# TMC5130_3D_Printer_BOARD_V_2.net
KiCad netlist of a schematic drawn in EAGLE
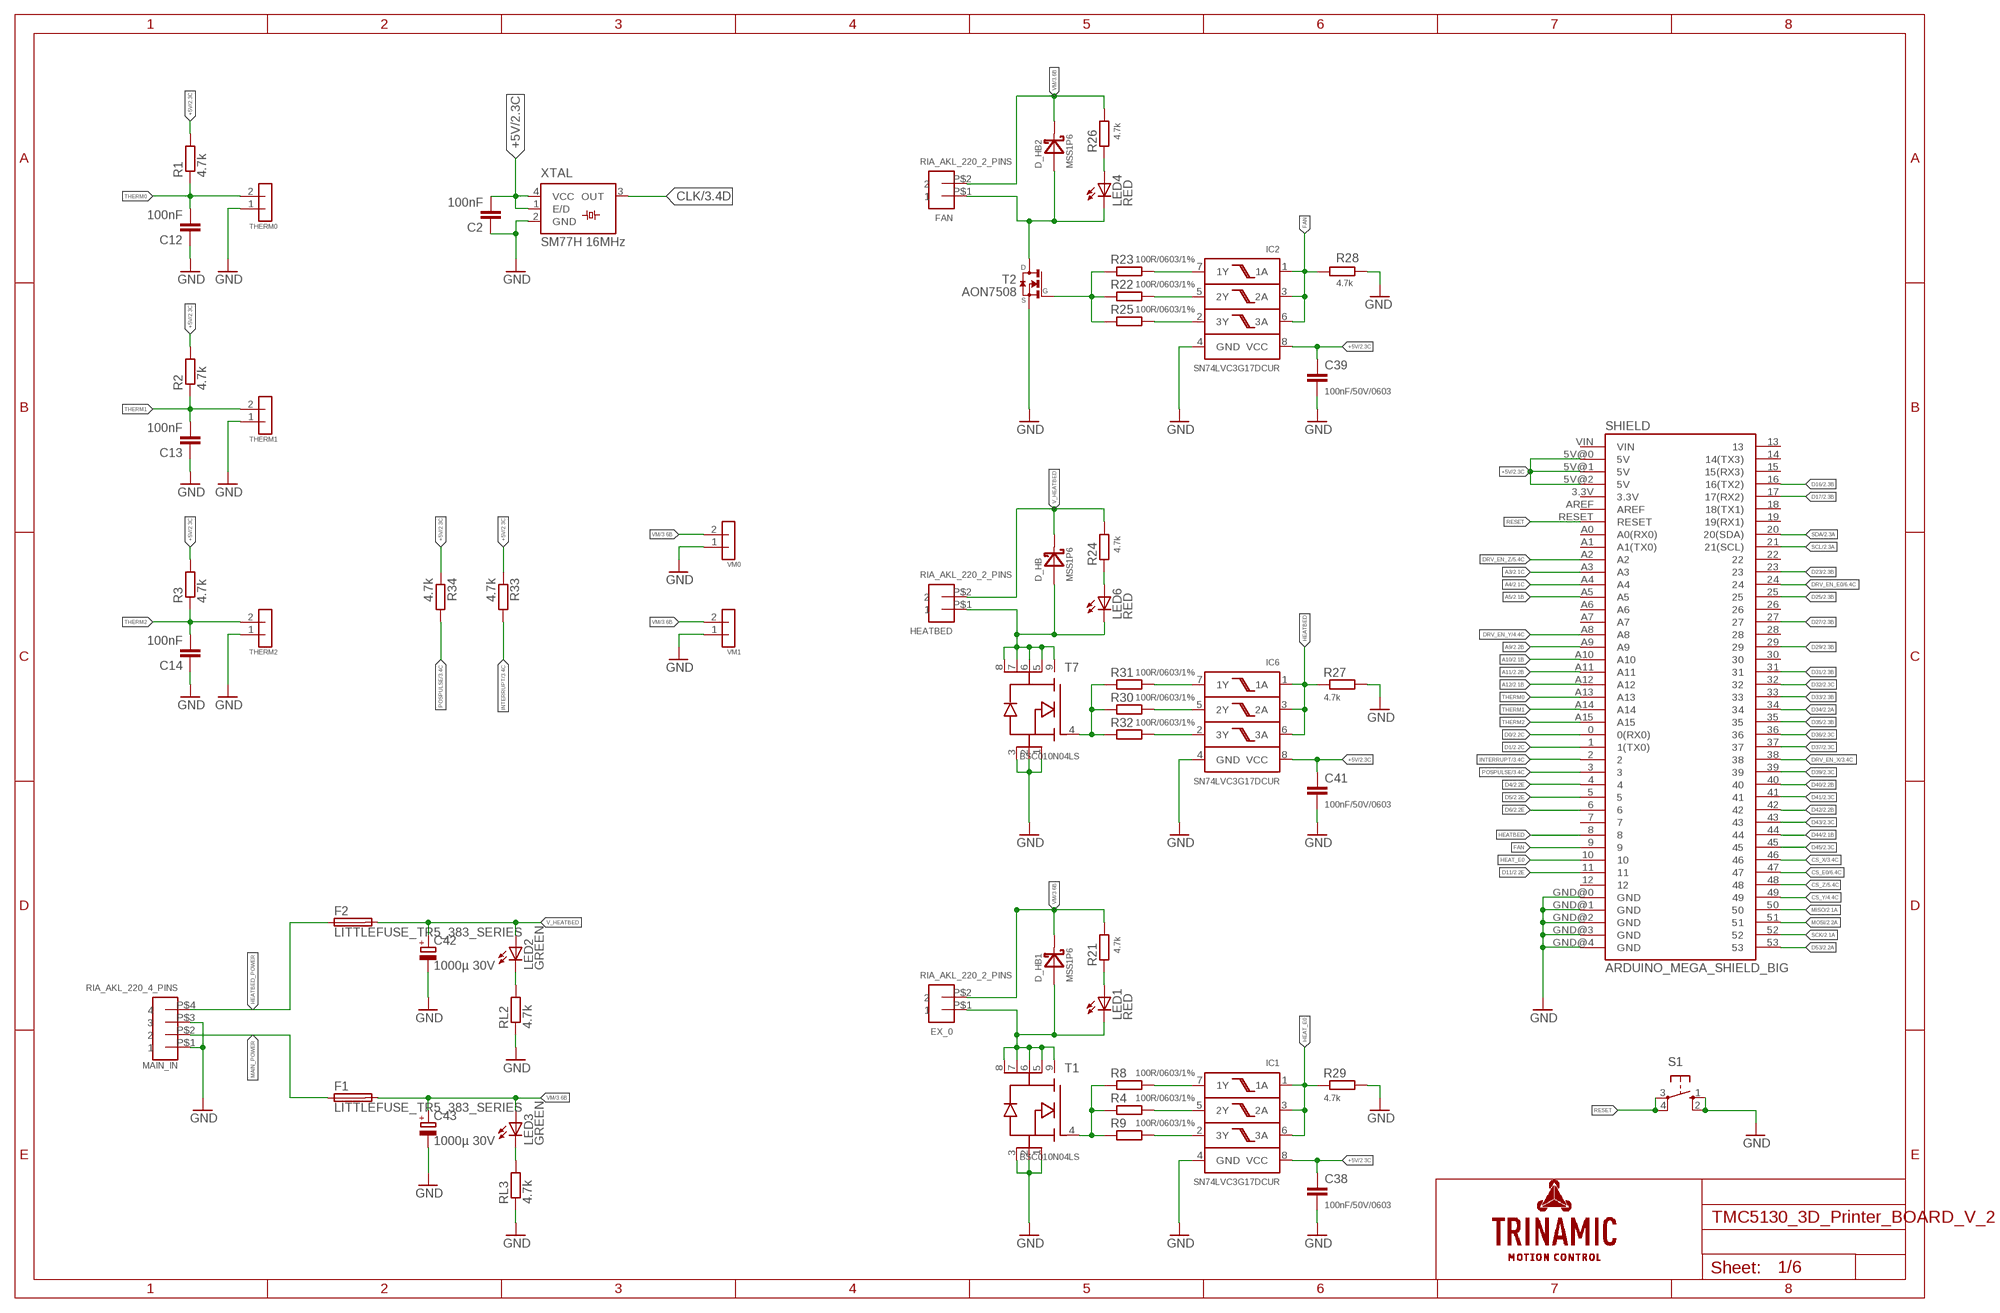
[diagram p0: schematic, sheet 1]
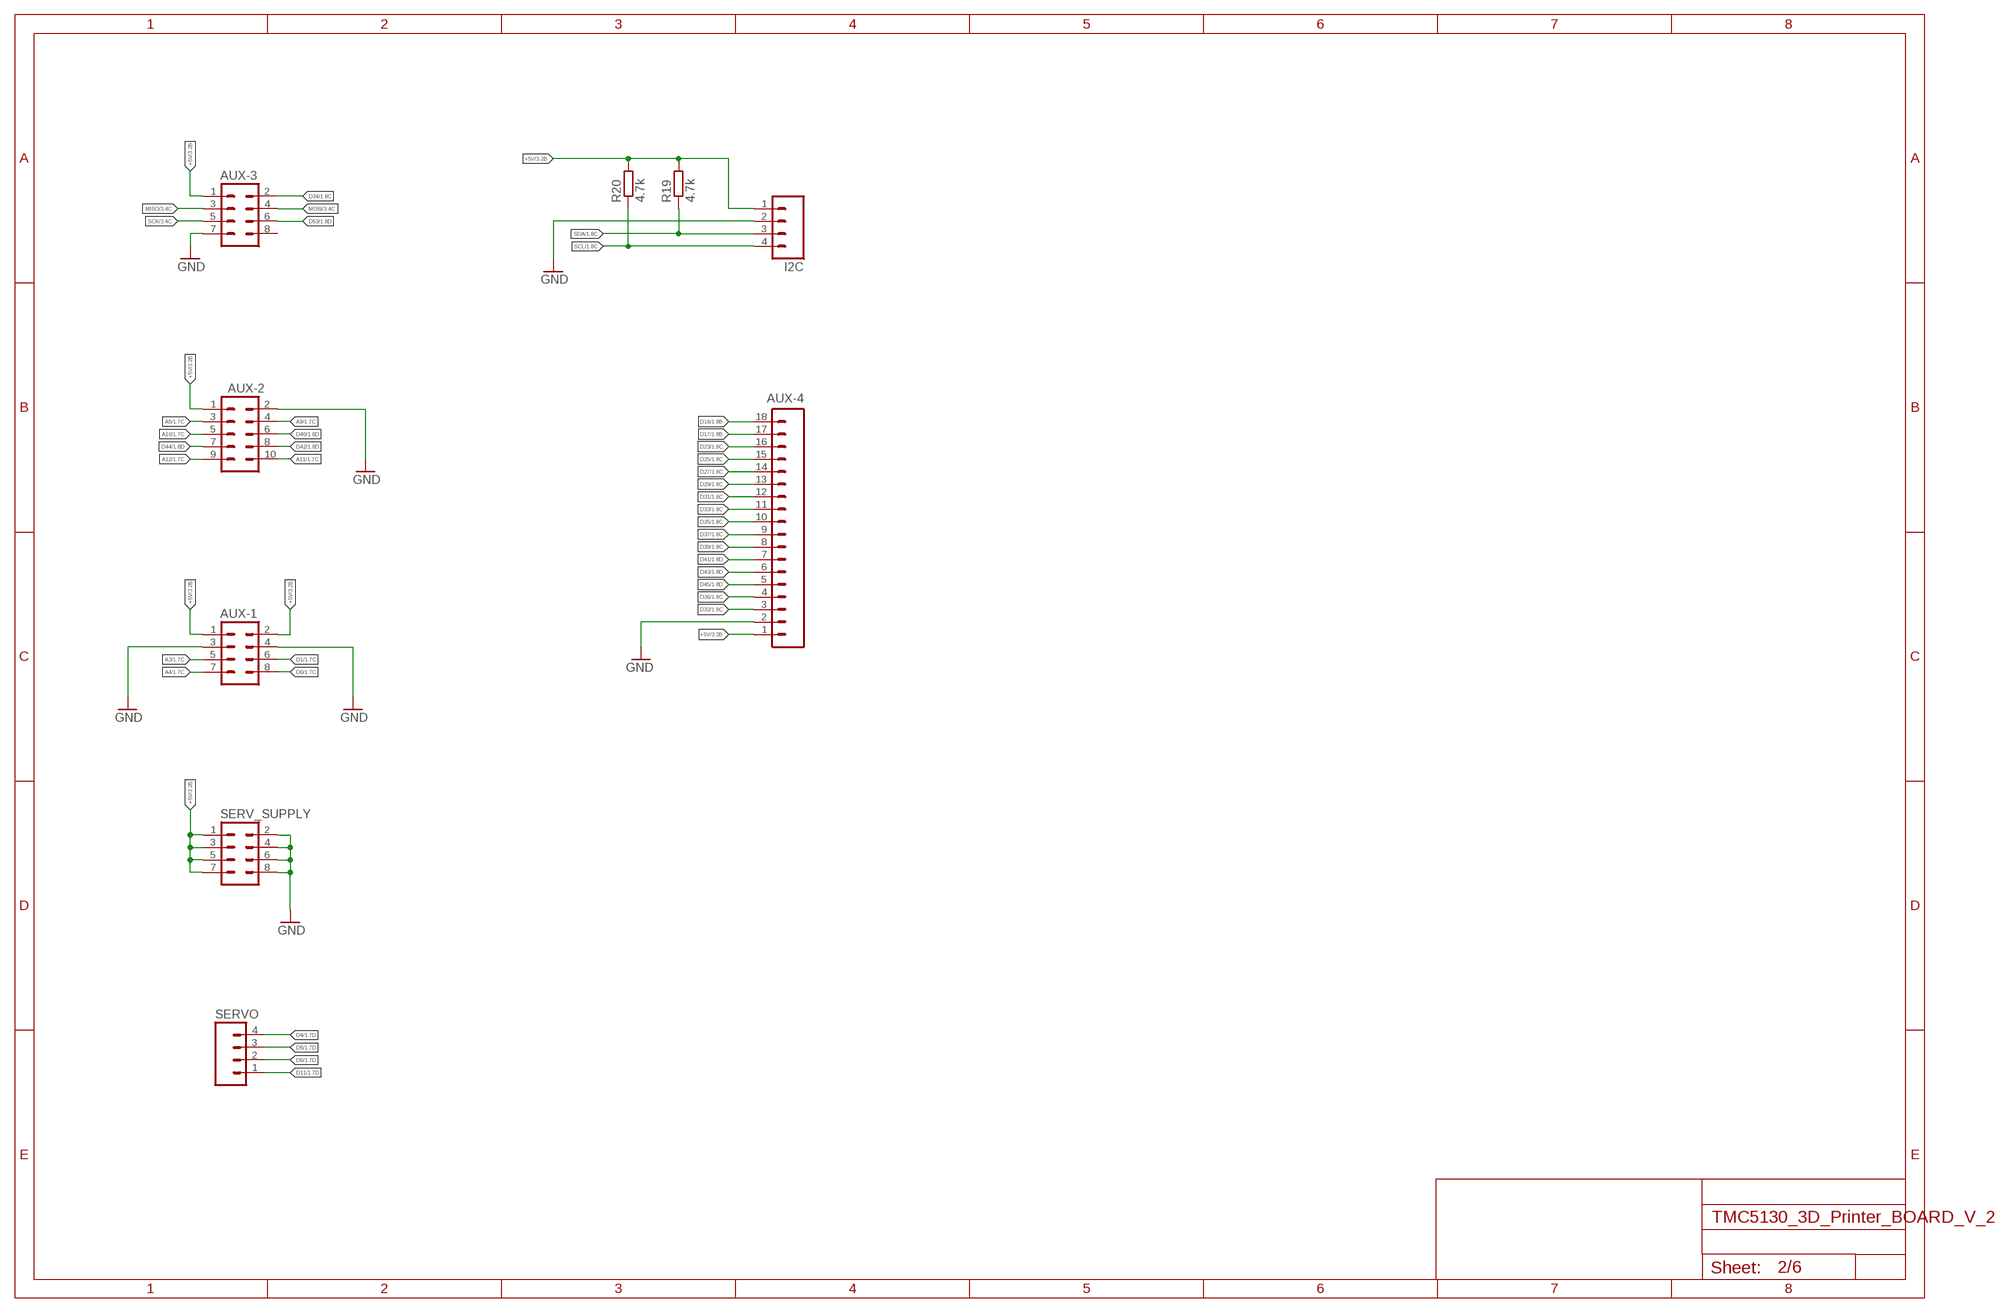
[diagram p1: schematic, sheet 2]
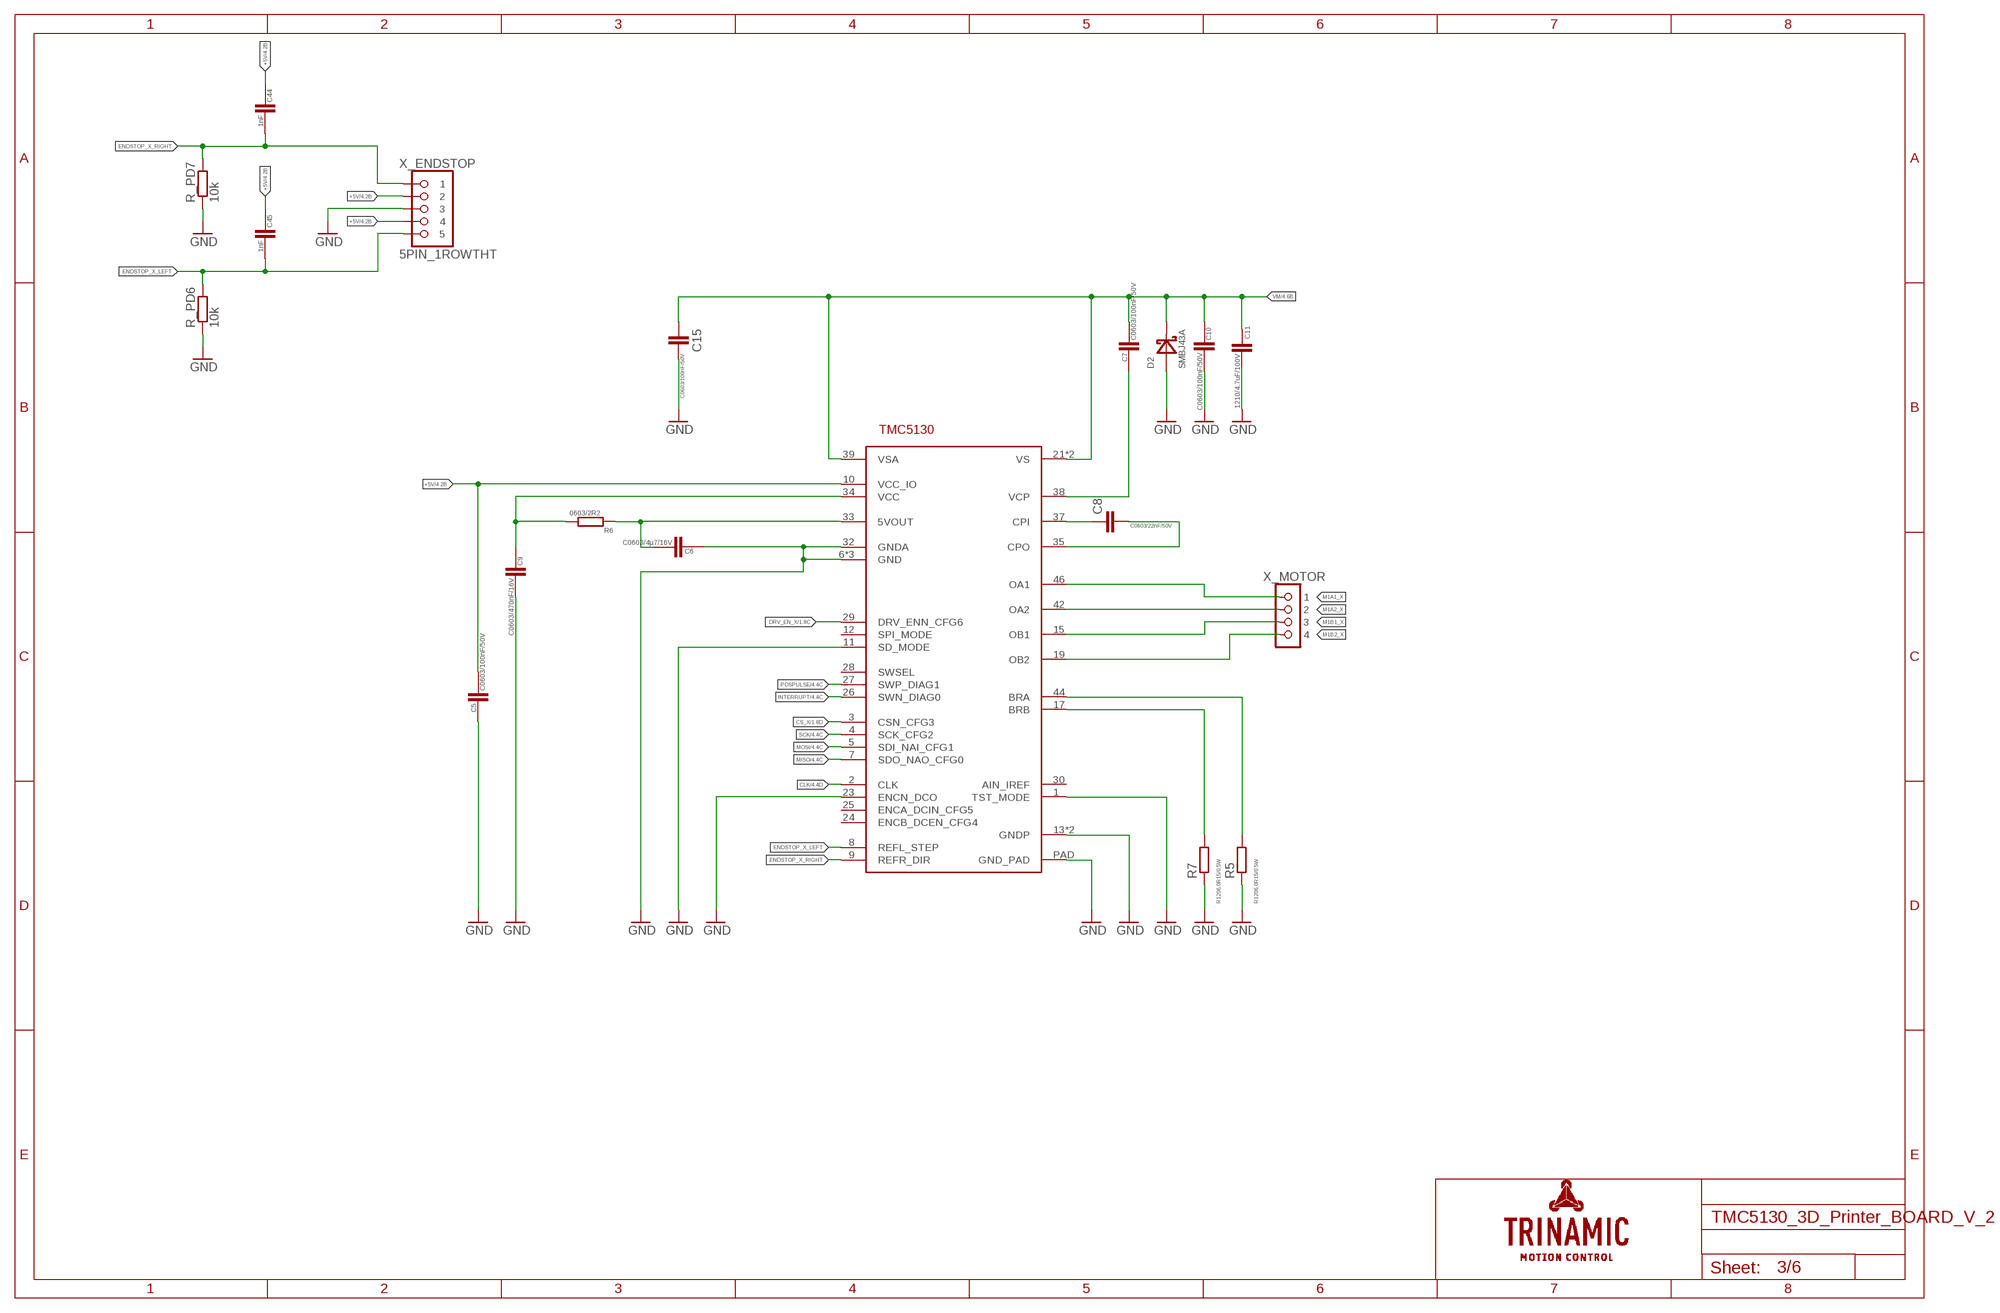
[diagram p2: schematic, sheet 3]
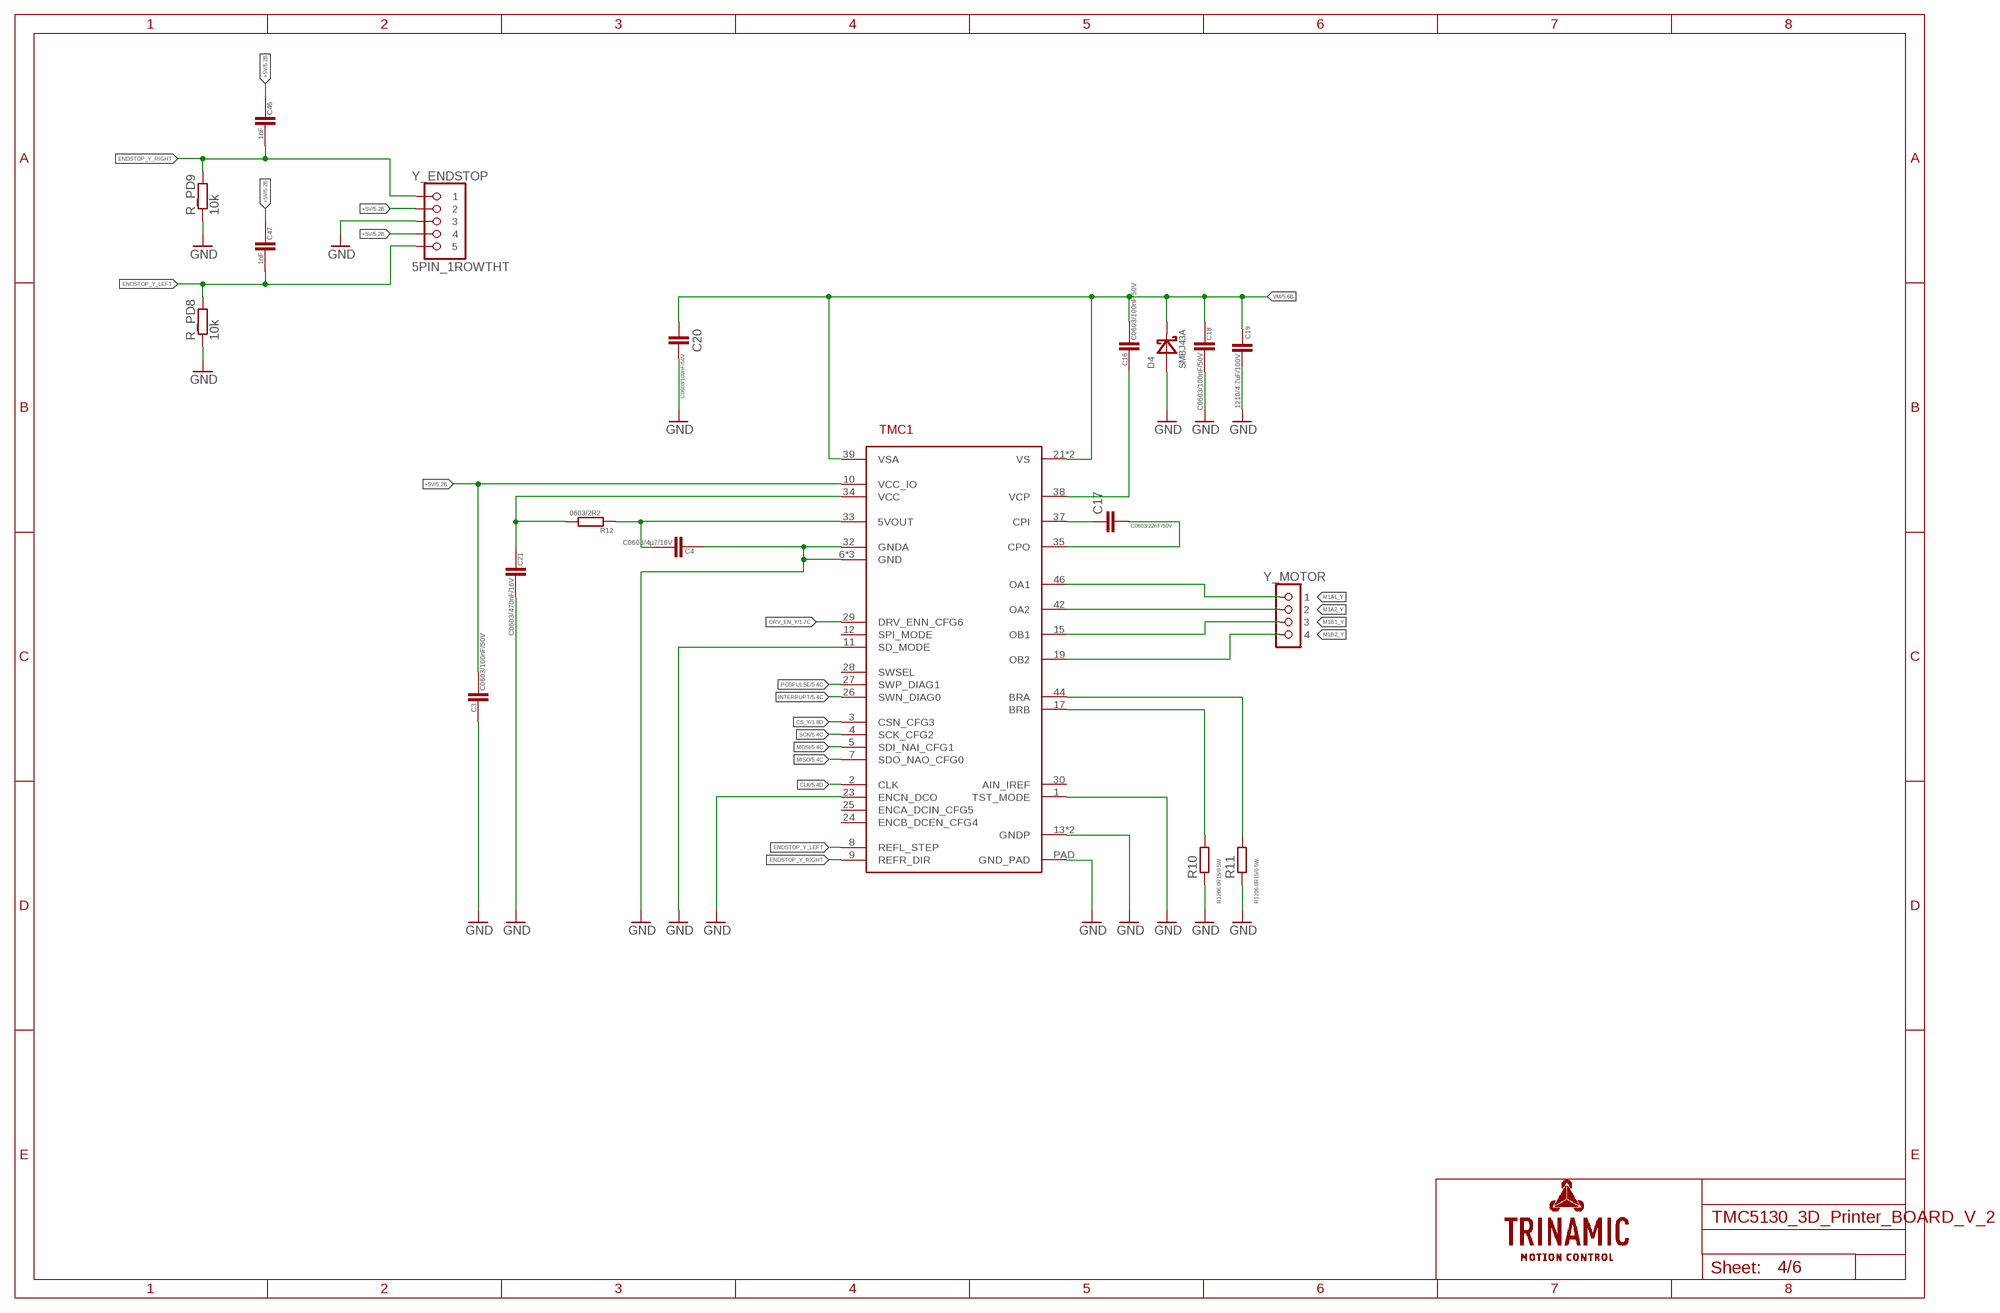
[diagram p3: schematic, sheet 4]
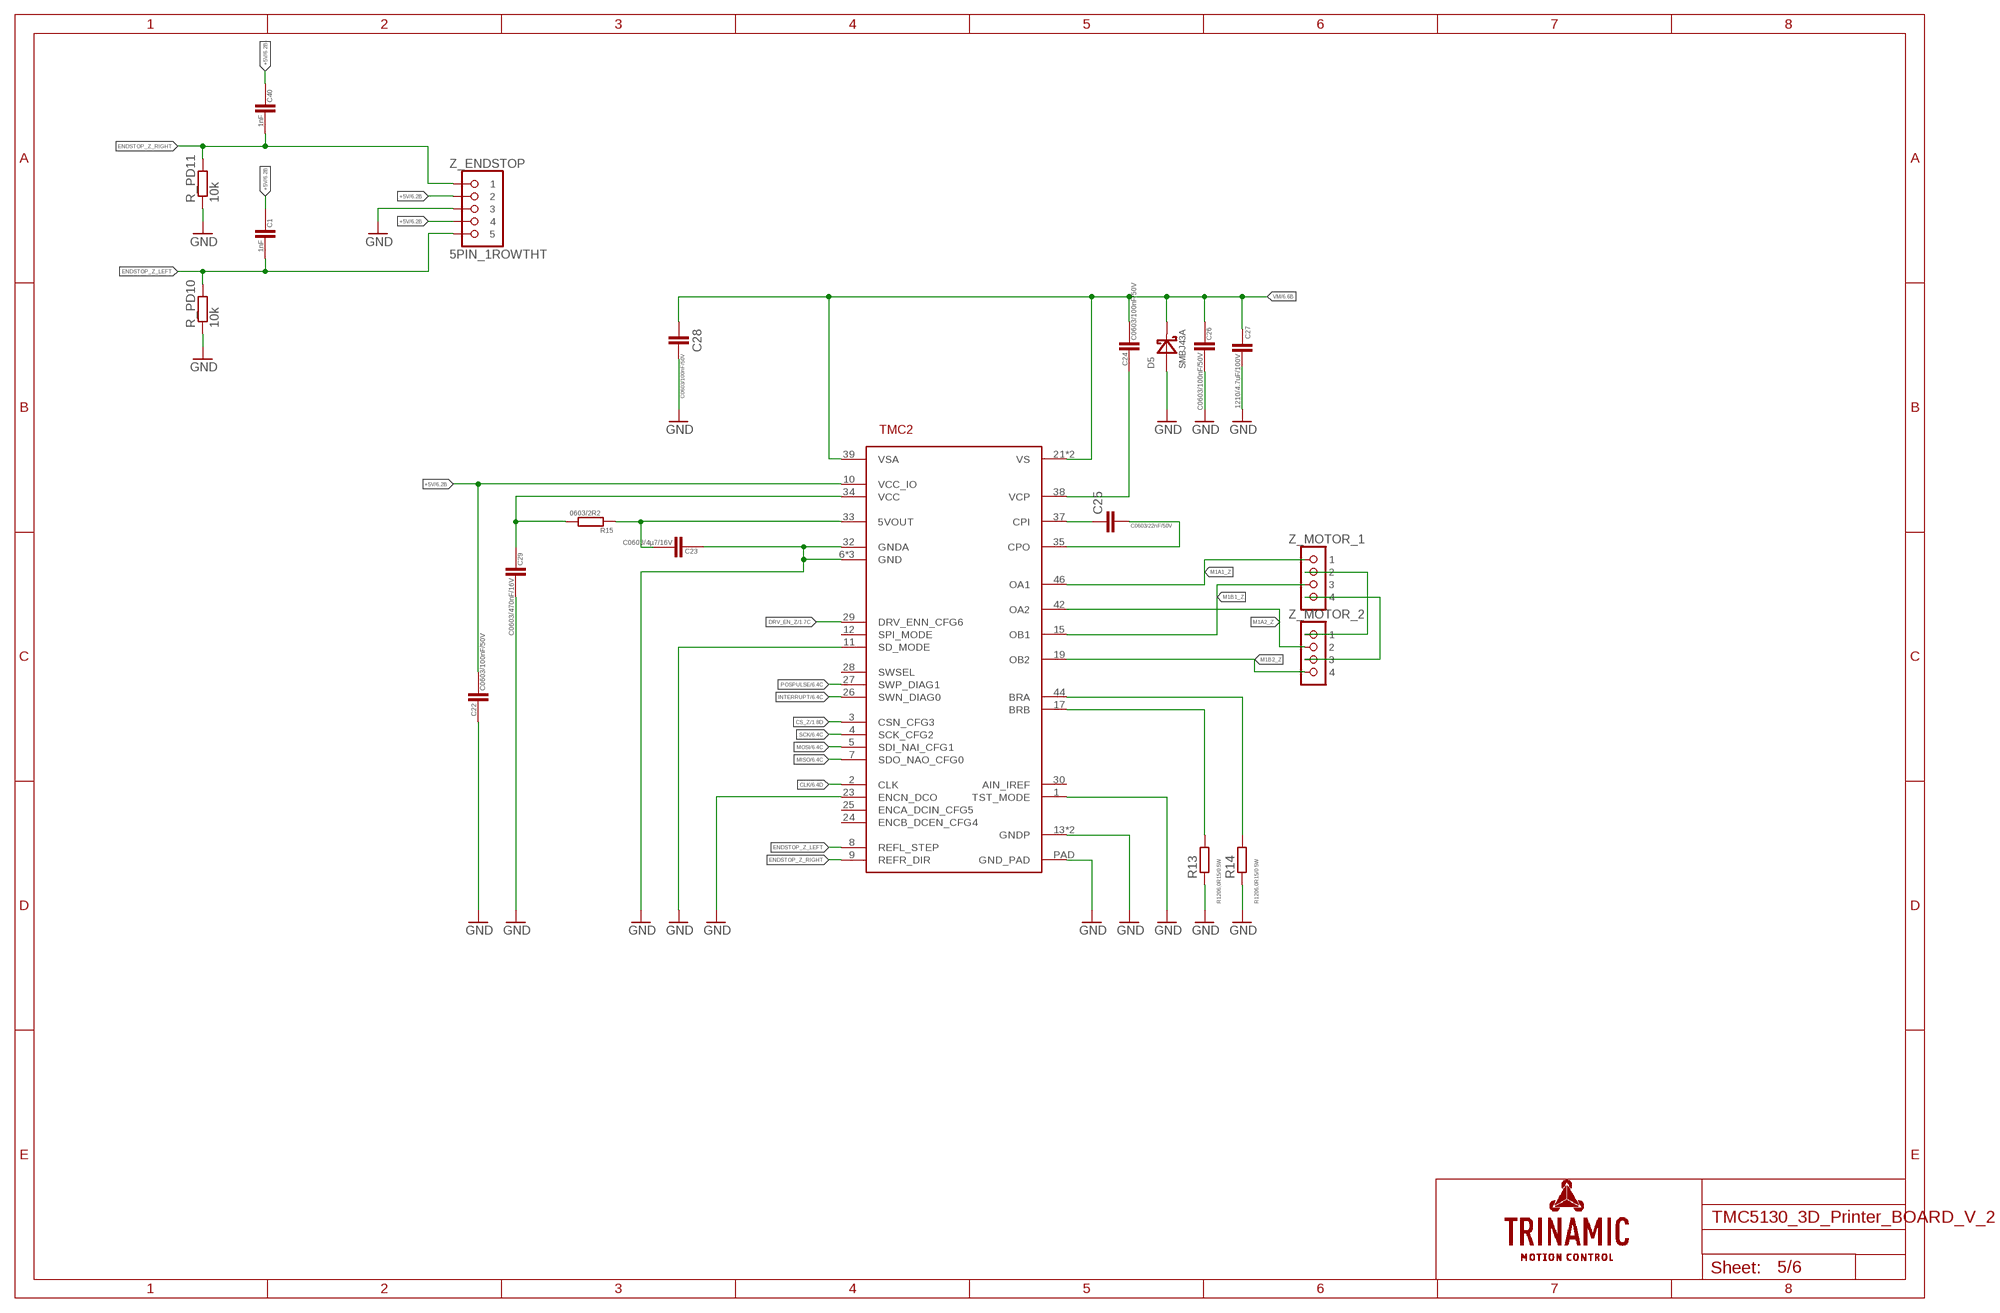
[diagram p4: schematic, sheet 5]
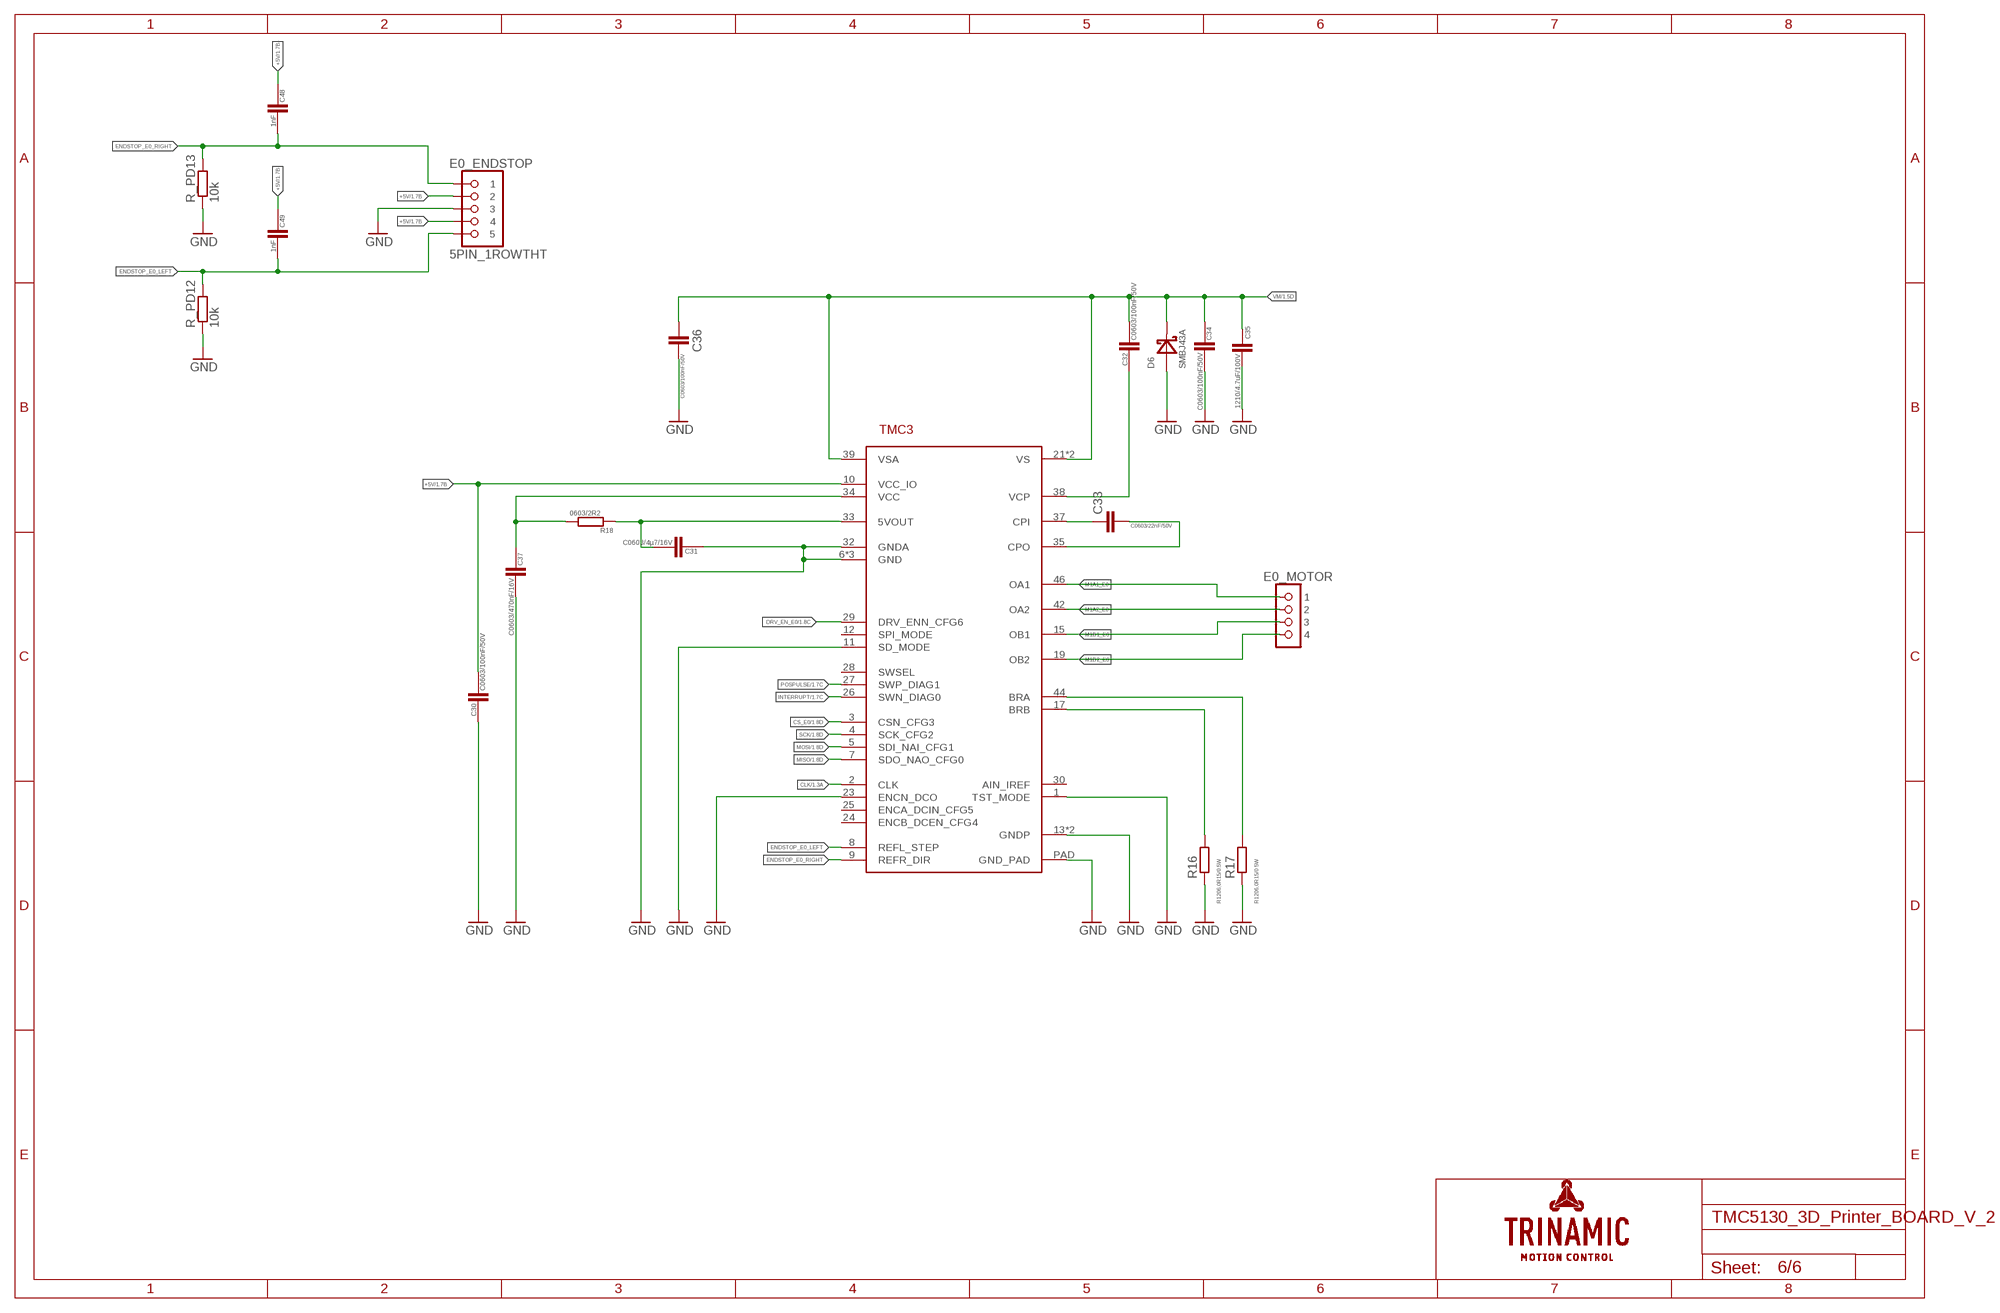
[diagram p5: schematic, sheet 6]

(export (version "E")
  (design (tool "Eeschema 10.0.6"))
  (components
    (comp (ref "C2")
      (value "100nF")
      (footprint "eagle-import:C0603")
      (libsource (lib "eagle-import") (part "C-EUC0603"))
    )
    (comp (ref "C12")
      (value "100nF")
      (footprint "eagle-import:C0603")
      (libsource (lib "eagle-import") (part "C-EUC0603"))
    )
    (comp (ref "C13")
      (value "100nF")
      (footprint "eagle-import:C0603")
      (libsource (lib "eagle-import") (part "C-EUC0603"))
    )
    (comp (ref "C14")
      (value "100nF")
      (footprint "eagle-import:C0603")
      (libsource (lib "eagle-import") (part "C-EUC0603"))
    )
    (comp (ref "C38")
      (value "100nF/50V/0603")
      (footprint "eagle-import:C0603")
      (libsource (lib "eagle-import") (part "C-EUC0603"))
    )
    (comp (ref "C39")
      (value "100nF/50V/0603")
      (footprint "eagle-import:C0603")
      (libsource (lib "eagle-import") (part "C-EUC0603"))
    )
    (comp (ref "C41")
      (value "100nF/50V/0603")
      (footprint "eagle-import:C0603")
      (libsource (lib "eagle-import") (part "C-EUC0603"))
    )
    (comp (ref "C42")
      (value "1000µ 30V")
      (footprint "eagle-import:E5-10,5")
      (libsource (lib "eagle-import") (part "CPOL-EUE5-10.5"))
    )
    (comp (ref "C43")
      (value "1000µ 30V")
      (footprint "eagle-import:E5-10,5")
      (libsource (lib "eagle-import") (part "CPOL-EUE5-10.5"))
    )
    (comp (ref "D_HB")
      (value "MSS1P6")
      (footprint "eagle-import:MICRO_SMP")
      (libsource (lib "eagle-import") (part "MSS1P6"))
    )
    (comp (ref "D_HB1")
      (value "MSS1P6")
      (footprint "eagle-import:MICRO_SMP")
      (libsource (lib "eagle-import") (part "MSS1P6"))
    )
    (comp (ref "D_HB2")
      (value "MSS1P6")
      (footprint "eagle-import:MICRO_SMP")
      (libsource (lib "eagle-import") (part "MSS1P6"))
    )
    (comp (ref "EX_0")
      (value "RIA_AKL_220_2_PINS")
      (footprint "eagle-import:RIA_AKL_220_2_PINS")
      (libsource (lib "eagle-import") (part "RIA_AKL_220_2_PINS"))
    )
    (comp (ref "F1")
      (value "LITTLEFUSE_TR5_383_SERIES")
      (footprint "eagle-import:LITTLEFUSE_TR5_383_SERIES")
      (libsource (lib "eagle-import") (part "LITTLEFUSE_TR5_383_SERIES"))
    )
    (comp (ref "F2")
      (value "LITTLEFUSE_TR5_383_SERIES")
      (footprint "eagle-import:LITTLEFUSE_TR5_383_SERIES")
      (libsource (lib "eagle-import") (part "LITTLEFUSE_TR5_383_SERIES"))
    )
    (comp (ref "FAN")
      (value "RIA_AKL_220_2_PINS")
      (footprint "eagle-import:RIA_AKL_220_2_PINS")
      (libsource (lib "eagle-import") (part "RIA_AKL_220_2_PINS"))
    )
    (comp (ref "HEATBED")
      (value "RIA_AKL_220_2_PINS")
      (footprint "eagle-import:RIA_AKL_220_2_PINS")
      (libsource (lib "eagle-import") (part "RIA_AKL_220_2_PINS"))
    )
    (comp (ref "IC1")
      (value "SN74LVC3G17DCUR")
      (footprint "eagle-import:US8_DCU")
      (libsource (lib "eagle-import") (part "SN74LVC3G17DCUR"))
    )
    (comp (ref "IC2")
      (value "SN74LVC3G17DCUR")
      (footprint "eagle-import:US8_DCU")
      (libsource (lib "eagle-import") (part "SN74LVC3G17DCUR"))
    )
    (comp (ref "IC6")
      (value "SN74LVC3G17DCUR")
      (footprint "eagle-import:US8_DCU")
      (libsource (lib "eagle-import") (part "SN74LVC3G17DCUR"))
    )
    (comp (ref "LED1")
      (value "RED")
      (footprint "eagle-import:CHIPLED_0603")
      (libsource (lib "eagle-import") (part "LEDCHIPLED_0603"))
    )
    (comp (ref "LED2")
      (value "GREEN")
      (footprint "eagle-import:CHIPLED_0603")
      (libsource (lib "eagle-import") (part "LEDCHIPLED_0603"))
    )
    (comp (ref "LED3")
      (value "GREEN")
      (footprint "eagle-import:CHIPLED_0603")
      (libsource (lib "eagle-import") (part "LEDCHIPLED_0603"))
    )
    (comp (ref "LED4")
      (value "RED")
      (footprint "eagle-import:CHIPLED_0603")
      (libsource (lib "eagle-import") (part "LEDCHIPLED_0603"))
    )
    (comp (ref "LED6")
      (value "RED")
      (footprint "eagle-import:CHIPLED_0603")
      (libsource (lib "eagle-import") (part "LEDCHIPLED_0603"))
    )
    (comp (ref "MAIN_IN")
      (value "RIA_AKL_220_4_PINS")
      (footprint "eagle-import:RIA_AKL_220_4_PINS")
      (libsource (lib "eagle-import") (part "RIA_AKL_220_4_PINS"))
    )
    (comp (ref "R1")
      (value "4.7k")
      (footprint "eagle-import:R0603")
      (libsource (lib "eagle-import") (part "R-EU_R0603"))
    )
    (comp (ref "R2")
      (value "4.7k")
      (footprint "eagle-import:R0603")
      (libsource (lib "eagle-import") (part "R-EU_R0603"))
    )
    (comp (ref "R3")
      (value "4.7k")
      (footprint "eagle-import:R0603")
      (libsource (lib "eagle-import") (part "R-EU_R0603"))
    )
    (comp (ref "R4")
      (value "100R/0603/1%")
      (footprint "eagle-import:R0603")
      (libsource (lib "eagle-import") (part "R-EU_R0603"))
    )
    (comp (ref "R8")
      (value "100R/0603/1%")
      (footprint "eagle-import:R0603")
      (libsource (lib "eagle-import") (part "R-EU_R0603"))
    )
    (comp (ref "R9")
      (value "100R/0603/1%")
      (footprint "eagle-import:R0603")
      (libsource (lib "eagle-import") (part "R-EU_R0603"))
    )
    (comp (ref "R21")
      (value "4.7k")
      (footprint "eagle-import:R0603")
      (libsource (lib "eagle-import") (part "R-EU_R0603"))
    )
    (comp (ref "R22")
      (value "100R/0603/1%")
      (footprint "eagle-import:R0603")
      (libsource (lib "eagle-import") (part "R-EU_R0603"))
    )
    (comp (ref "R23")
      (value "100R/0603/1%")
      (footprint "eagle-import:R0603")
      (libsource (lib "eagle-import") (part "R-EU_R0603"))
    )
    (comp (ref "R24")
      (value "4.7k")
      (footprint "eagle-import:R0603")
      (libsource (lib "eagle-import") (part "R-EU_R0603"))
    )
    (comp (ref "R25")
      (value "100R/0603/1%")
      (footprint "eagle-import:R0603")
      (libsource (lib "eagle-import") (part "R-EU_R0603"))
    )
    (comp (ref "R26")
      (value "4.7k")
      (footprint "eagle-import:R0603")
      (libsource (lib "eagle-import") (part "R-EU_R0603"))
    )
    (comp (ref "R27")
      (value "4.7k")
      (footprint "eagle-import:R0603")
      (libsource (lib "eagle-import") (part "R-EU_R0603"))
    )
    (comp (ref "R28")
      (value "4.7k")
      (footprint "eagle-import:R0603")
      (libsource (lib "eagle-import") (part "R-EU_R0603"))
    )
    (comp (ref "R29")
      (value "4.7k")
      (footprint "eagle-import:R0603")
      (libsource (lib "eagle-import") (part "R-EU_R0603"))
    )
    (comp (ref "R30")
      (value "100R/0603/1%")
      (footprint "eagle-import:R0603")
      (libsource (lib "eagle-import") (part "R-EU_R0603"))
    )
    (comp (ref "R31")
      (value "100R/0603/1%")
      (footprint "eagle-import:R0603")
      (libsource (lib "eagle-import") (part "R-EU_R0603"))
    )
    (comp (ref "R32")
      (value "100R/0603/1%")
      (footprint "eagle-import:R0603")
      (libsource (lib "eagle-import") (part "R-EU_R0603"))
    )
    (comp (ref "R33")
      (value "4.7k")
      (footprint "eagle-import:R0603")
      (libsource (lib "eagle-import") (part "R-EU_R0603"))
    )
    (comp (ref "R34")
      (value "4.7k")
      (footprint "eagle-import:R0603")
      (libsource (lib "eagle-import") (part "R-EU_R0603"))
    )
    (comp (ref "RL2")
      (value "4.7k")
      (footprint "eagle-import:R0603")
      (libsource (lib "eagle-import") (part "R-EU_R0603"))
    )
    (comp (ref "RL3")
      (value "4.7k")
      (footprint "eagle-import:R0603")
      (libsource (lib "eagle-import") (part "R-EU_R0603"))
    )
    (comp (ref "S1")
      (value "10-XX")
      (footprint "eagle-import:B3F-10XX")
      (fields (field (name "MPN") "B3F-1000"))
      (libsource (lib "eagle-import") (part "10-XX"))
    )
    (comp (ref "SHIELD")
      (value "ARDUINO_MEGA_SHIELD_BIG")
      (footprint "eagle-import:ARDUINO_MEGA_SHIELD")
      (libsource (lib "eagle-import") (part "ARDUINO_MEGA_SHIELD_BIG"))
    )
    (comp (ref "T1")
      (value "BSC010N04LS")
      (footprint "eagle-import:PG-TDSON-8FL")
      (libsource (lib "eagle-import") (part "BSC010N04LS"))
    )
    (comp (ref "T2")
      (value "AON7508")
      (footprint "eagle-import:DFN3X3_8L")
      (libsource (lib "eagle-import") (part "AON7508"))
    )
    (comp (ref "T7")
      (value "BSC010N04LS")
      (footprint "eagle-import:PG-TDSON-8FL")
      (libsource (lib "eagle-import") (part "BSC010N04LS"))
    )
    (comp (ref "THERM0")
      (value "2PIN_1ROW")
      (footprint "eagle-import:2PIN_1ROW_2.54_THT")
      (libsource (lib "eagle-import") (part "2PIN_1ROW"))
    )
    (comp (ref "THERM1")
      (value "2PIN_1ROW")
      (footprint "eagle-import:2PIN_1ROW_2.54_THT")
      (libsource (lib "eagle-import") (part "2PIN_1ROW"))
    )
    (comp (ref "THERM2")
      (value "2PIN_1ROW")
      (footprint "eagle-import:2PIN_1ROW_2.54_THT")
      (libsource (lib "eagle-import") (part "2PIN_1ROW"))
    )
    (comp (ref "VM0")
      (value "2PIN_1ROW")
      (footprint "eagle-import:2PIN_1ROW_2.54_THT")
      (libsource (lib "eagle-import") (part "2PIN_1ROW"))
    )
    (comp (ref "VM1")
      (value "2PIN_1ROW")
      (footprint "eagle-import:2PIN_1ROW_2.54_THT")
      (libsource (lib "eagle-import") (part "2PIN_1ROW"))
    )
    (comp (ref "XTAL")
      (value "SM77H 16MHz")
      (footprint "eagle-import:SM77H")
      (libsource (lib "eagle-import") (part "SM77H"))
    )
    (comp (ref "C3")
      (value "C0603/100nF/50V")
      (footprint "eagle-import:0603")
      (libsource (lib "eagle-import") (part "C/0603"))
    )
    (comp (ref "C4")
      (value "C0603/4µ7/16V")
      (footprint "eagle-import:0603")
      (libsource (lib "eagle-import") (part "C/0603"))
    )
    (comp (ref "C16")
      (value "C0603/100nF/50V")
      (footprint "eagle-import:0603")
      (libsource (lib "eagle-import") (part "C/0603"))
    )
    (comp (ref "C17")
      (value "C0603/22nF/50V")
      (footprint "eagle-import:C0603")
      (libsource (lib "eagle-import") (part "C-EUC0603"))
    )
    (comp (ref "C18")
      (value "C0603/100nF/50V")
      (footprint "eagle-import:0603")
      (libsource (lib "eagle-import") (part "C/0603"))
    )
    (comp (ref "C19")
      (value "1210/4.7uF/100V")
      (footprint "eagle-import:C1210")
      (libsource (lib "eagle-import") (part "C-EUC1210"))
    )
    (comp (ref "C20")
      (value "C0603/100nF/50V")
      (footprint "eagle-import:C0603")
      (libsource (lib "eagle-import") (part "C-EUC0603"))
    )
    (comp (ref "C21")
      (value "C0603/470nF/16V")
      (footprint "eagle-import:0603")
      (libsource (lib "eagle-import") (part "C/0603"))
    )
    (comp (ref "C46")
      (value "1nF")
      (footprint "eagle-import:0603")
      (libsource (lib "eagle-import") (part "C/0603"))
    )
    (comp (ref "C47")
      (value "1nF")
      (footprint "eagle-import:0603")
      (libsource (lib "eagle-import") (part "C/0603"))
    )
    (comp (ref "D4")
      (value "SMBJ43A")
      (footprint "eagle-import:SMB")
      (libsource (lib "eagle-import") (part "SMBJ"))
    )
    (comp (ref "R10")
      (value "R1206,0R15/0.5W")
      (footprint "eagle-import:R1206")
      (libsource (lib "eagle-import") (part "R-EU_R1206"))
    )
    (comp (ref "R11")
      (value "R1206,0R15/0.5W")
      (footprint "eagle-import:R1206")
      (libsource (lib "eagle-import") (part "R-EU_R1206"))
    )
    (comp (ref "R12")
      (value "0603/2R2")
      (footprint "eagle-import:0603")
      (libsource (lib "eagle-import") (part "R/0603"))
    )
    (comp (ref "R_PD8")
      (value "10k")
      (footprint "eagle-import:R0603")
      (libsource (lib "eagle-import") (part "R-EU_R0603"))
    )
    (comp (ref "R_PD9")
      (value "10k")
      (footprint "eagle-import:R0603")
      (libsource (lib "eagle-import") (part "R-EU_R0603"))
    )
    (comp (ref "TMC1")
      (value "TMC5130")
      (footprint "eagle-import:QFP50P900X900X113-49N_NOFID")
      (libsource (lib "eagle-import") (part "TMC5130"))
    )
    (comp (ref "Y_ENDSTOP")
      (value "5PIN_1ROWTHT")
      (footprint "eagle-import:5PIN_1ROW_2.54_THT")
      (libsource (lib "eagle-import") (part "5PIN_1ROWTHT"))
    )
    (comp (ref "Y_MOTOR")
      (value "4PIN_1ROWTHT")
      (footprint "eagle-import:4PIN_1ROW_2.54_THT")
      (libsource (lib "eagle-import") (part "4PIN_1ROWTHT"))
    )
    (comp (ref "C30")
      (value "C0603/100nF/50V")
      (footprint "eagle-import:0603")
      (libsource (lib "eagle-import") (part "C/0603"))
    )
    (comp (ref "C31")
      (value "C0603/4µ7/16V")
      (footprint "eagle-import:0603")
      (libsource (lib "eagle-import") (part "C/0603"))
    )
    (comp (ref "C32")
      (value "C0603/100nF/50V")
      (footprint "eagle-import:0603")
      (libsource (lib "eagle-import") (part "C/0603"))
    )
    (comp (ref "C33")
      (value "C0603/22nF/50V")
      (footprint "eagle-import:C0603")
      (libsource (lib "eagle-import") (part "C-EUC0603"))
    )
    (comp (ref "C34")
      (value "C0603/100nF/50V")
      (footprint "eagle-import:0603")
      (libsource (lib "eagle-import") (part "C/0603"))
    )
    (comp (ref "C35")
      (value "1210/4.7uF/100V")
      (footprint "eagle-import:C1210")
      (libsource (lib "eagle-import") (part "C-EUC1210"))
    )
    (comp (ref "C36")
      (value "C0603/100nF/50V")
      (footprint "eagle-import:C0603")
      (libsource (lib "eagle-import") (part "C-EUC0603"))
    )
    (comp (ref "C37")
      (value "C0603/470nF/16V")
      (footprint "eagle-import:0603")
      (libsource (lib "eagle-import") (part "C/0603"))
    )
    (comp (ref "C48")
      (value "1nF")
      (footprint "eagle-import:0603")
      (libsource (lib "eagle-import") (part "C/0603"))
    )
    (comp (ref "C49")
      (value "1nF")
      (footprint "eagle-import:0603")
      (libsource (lib "eagle-import") (part "C/0603"))
    )
    (comp (ref "D6")
      (value "SMBJ43A")
      (footprint "eagle-import:SMB")
      (libsource (lib "eagle-import") (part "SMBJ"))
    )
    (comp (ref "E0_ENDSTOP")
      (value "5PIN_1ROWTHT")
      (footprint "eagle-import:5PIN_1ROW_2.54_THT")
      (libsource (lib "eagle-import") (part "5PIN_1ROWTHT"))
    )
    (comp (ref "E0_MOTOR")
      (value "4PIN_1ROWTHT")
      (footprint "eagle-import:4PIN_1ROW_2.54_THT")
      (libsource (lib "eagle-import") (part "4PIN_1ROWTHT"))
    )
    (comp (ref "R16")
      (value "R1206,0R15/0.5W")
      (footprint "eagle-import:R1206")
      (libsource (lib "eagle-import") (part "R-EU_R1206"))
    )
    (comp (ref "R17")
      (value "R1206,0R15/0.5W")
      (footprint "eagle-import:R1206")
      (libsource (lib "eagle-import") (part "R-EU_R1206"))
    )
    (comp (ref "R18")
      (value "0603/2R2")
      (footprint "eagle-import:0603")
      (libsource (lib "eagle-import") (part "R/0603"))
    )
    (comp (ref "R_PD12")
      (value "10k")
      (footprint "eagle-import:R0603")
      (libsource (lib "eagle-import") (part "R-EU_R0603"))
    )
    (comp (ref "R_PD13")
      (value "10k")
      (footprint "eagle-import:R0603")
      (libsource (lib "eagle-import") (part "R-EU_R0603"))
    )
    (comp (ref "TMC3")
      (value "TMC5130")
      (footprint "eagle-import:QFP50P900X900X113-49N_NOFID")
      (libsource (lib "eagle-import") (part "TMC5130"))
    )
    (comp (ref "AUX-1")
      (value "M04X2")
      (footprint "eagle-import:2X4")
      (libsource (lib "eagle-import") (part "M04X2"))
    )
    (comp (ref "AUX-2")
      (value "M05X2PTH")
      (footprint "eagle-import:AVR_ICSP")
      (libsource (lib "eagle-import") (part "M05X2PTH"))
    )
    (comp (ref "AUX-3")
      (value "M04X2")
      (footprint "eagle-import:2X4")
      (libsource (lib "eagle-import") (part "M04X2"))
    )
    (comp (ref "AUX-4")
      (value "M18_")
      (footprint "eagle-import:1X18")
      (libsource (lib "eagle-import") (part "M18_"))
    )
    (comp (ref "I2C")
      (value "M04PTH")
      (footprint "eagle-import:1X04")
      (libsource (lib "eagle-import") (part "M04PTH"))
    )
    (comp (ref "R19")
      (value "4.7k")
      (footprint "eagle-import:R0603")
      (libsource (lib "eagle-import") (part "R-EU_R0603"))
    )
    (comp (ref "R20")
      (value "4.7k")
      (footprint "eagle-import:R0603")
      (libsource (lib "eagle-import") (part "R-EU_R0603"))
    )
    (comp (ref "SERVO")
      (value "M04PTH")
      (footprint "eagle-import:1X04")
      (libsource (lib "eagle-import") (part "M04PTH"))
    )
    (comp (ref "SERV_SUPPLY")
      (value "M04X2")
      (footprint "eagle-import:2X4")
      (libsource (lib "eagle-import") (part "M04X2"))
    )
    (comp (ref "C5")
      (value "C0603/100nF/50V")
      (footprint "eagle-import:0603")
      (libsource (lib "eagle-import") (part "C/0603"))
    )
    (comp (ref "C6")
      (value "C0603/4µ7/16V")
      (footprint "eagle-import:0603")
      (libsource (lib "eagle-import") (part "C/0603"))
    )
    (comp (ref "C7")
      (value "C0603/100nF/50V")
      (footprint "eagle-import:0603")
      (libsource (lib "eagle-import") (part "C/0603"))
    )
    (comp (ref "C8")
      (value "C0603/22nF/50V")
      (footprint "eagle-import:C0603")
      (libsource (lib "eagle-import") (part "C-EUC0603"))
    )
    (comp (ref "C9")
      (value "C0603/470nF/16V")
      (footprint "eagle-import:0603")
      (libsource (lib "eagle-import") (part "C/0603"))
    )
    (comp (ref "C10")
      (value "C0603/100nF/50V")
      (footprint "eagle-import:0603")
      (libsource (lib "eagle-import") (part "C/0603"))
    )
    (comp (ref "C11")
      (value "1210/4.7uF/100V")
      (footprint "eagle-import:C1210")
      (libsource (lib "eagle-import") (part "C-EUC1210"))
    )
    (comp (ref "C15")
      (value "C0603/100nF/50V")
      (footprint "eagle-import:C0603")
      (libsource (lib "eagle-import") (part "C-EUC0603"))
    )
    (comp (ref "C44")
      (value "1nF")
      (footprint "eagle-import:0603")
      (libsource (lib "eagle-import") (part "C/0603"))
    )
    (comp (ref "C45")
      (value "1nF")
      (footprint "eagle-import:0603")
      (libsource (lib "eagle-import") (part "C/0603"))
    )
    (comp (ref "D2")
      (value "SMBJ43A")
      (footprint "eagle-import:SMB")
      (libsource (lib "eagle-import") (part "SMBJ"))
    )
    (comp (ref "R5")
      (value "R1206,0R15/0.5W")
      (footprint "eagle-import:R1206")
      (libsource (lib "eagle-import") (part "R-EU_R1206"))
    )
    (comp (ref "R6")
      (value "0603/2R2")
      (footprint "eagle-import:0603")
      (libsource (lib "eagle-import") (part "R/0603"))
    )
    (comp (ref "R7")
      (value "R1206,0R15/0.5W")
      (footprint "eagle-import:R1206")
      (libsource (lib "eagle-import") (part "R-EU_R1206"))
    )
    (comp (ref "R_PD6")
      (value "10k")
      (footprint "eagle-import:R0603")
      (libsource (lib "eagle-import") (part "R-EU_R0603"))
    )
    (comp (ref "R_PD7")
      (value "10k")
      (footprint "eagle-import:R0603")
      (libsource (lib "eagle-import") (part "R-EU_R0603"))
    )
    (comp (ref "TMC5130")
      (value "TMC5130")
      (footprint "eagle-import:QFP50P900X900X113-49N_NOFID")
      (libsource (lib "eagle-import") (part "TMC5130"))
    )
    (comp (ref "X_ENDSTOP")
      (value "5PIN_1ROWTHT")
      (footprint "eagle-import:5PIN_1ROW_2.54_THT")
      (libsource (lib "eagle-import") (part "5PIN_1ROWTHT"))
    )
    (comp (ref "X_MOTOR")
      (value "4PIN_1ROWTHT")
      (footprint "eagle-import:4PIN_1ROW_2.54_THT")
      (libsource (lib "eagle-import") (part "4PIN_1ROWTHT"))
    )
    (comp (ref "C1")
      (value "1nF")
      (footprint "eagle-import:0603")
      (libsource (lib "eagle-import") (part "C/0603"))
    )
    (comp (ref "C22")
      (value "C0603/100nF/50V")
      (footprint "eagle-import:0603")
      (libsource (lib "eagle-import") (part "C/0603"))
    )
    (comp (ref "C23")
      (value "C0603/4µ7/16V")
      (footprint "eagle-import:0603")
      (libsource (lib "eagle-import") (part "C/0603"))
    )
    (comp (ref "C24")
      (value "C0603/100nF/50V")
      (footprint "eagle-import:0603")
      (libsource (lib "eagle-import") (part "C/0603"))
    )
    (comp (ref "C25")
      (value "C0603/22nF/50V")
      (footprint "eagle-import:C0603")
      (libsource (lib "eagle-import") (part "C-EUC0603"))
    )
    (comp (ref "C26")
      (value "C0603/100nF/50V")
      (footprint "eagle-import:0603")
      (libsource (lib "eagle-import") (part "C/0603"))
    )
    (comp (ref "C27")
      (value "1210/4.7uF/100V")
      (footprint "eagle-import:C1210")
      (libsource (lib "eagle-import") (part "C-EUC1210"))
    )
    (comp (ref "C28")
      (value "C0603/100nF/50V")
      (footprint "eagle-import:C0603")
      (libsource (lib "eagle-import") (part "C-EUC0603"))
    )
    (comp (ref "C29")
      (value "C0603/470nF/16V")
      (footprint "eagle-import:0603")
      (libsource (lib "eagle-import") (part "C/0603"))
    )
    (comp (ref "C40")
      (value "1nF")
      (footprint "eagle-import:0603")
      (libsource (lib "eagle-import") (part "C/0603"))
    )
    (comp (ref "D5")
      (value "SMBJ43A")
      (footprint "eagle-import:SMB")
      (libsource (lib "eagle-import") (part "SMBJ"))
    )
    (comp (ref "R13")
      (value "R1206,0R15/0.5W")
      (footprint "eagle-import:R1206")
      (libsource (lib "eagle-import") (part "R-EU_R1206"))
    )
    (comp (ref "R14")
      (value "R1206,0R15/0.5W")
      (footprint "eagle-import:R1206")
      (libsource (lib "eagle-import") (part "R-EU_R1206"))
    )
    (comp (ref "R15")
      (value "0603/2R2")
      (footprint "eagle-import:0603")
      (libsource (lib "eagle-import") (part "R/0603"))
    )
    (comp (ref "R_PD10")
      (value "10k")
      (footprint "eagle-import:R0603")
      (libsource (lib "eagle-import") (part "R-EU_R0603"))
    )
    (comp (ref "R_PD11")
      (value "10k")
      (footprint "eagle-import:R0603")
      (libsource (lib "eagle-import") (part "R-EU_R0603"))
    )
    (comp (ref "TMC2")
      (value "TMC5130")
      (footprint "eagle-import:QFP50P900X900X113-49N_NOFID")
      (libsource (lib "eagle-import") (part "TMC5130"))
    )
    (comp (ref "Z_ENDSTOP")
      (value "5PIN_1ROWTHT")
      (footprint "eagle-import:5PIN_1ROW_2.54_THT")
      (libsource (lib "eagle-import") (part "5PIN_1ROWTHT"))
    )
    (comp (ref "Z_MOTOR_1")
      (value "4PIN_1ROWTHT")
      (footprint "eagle-import:4PIN_1ROW_2.54_THT")
      (libsource (lib "eagle-import") (part "4PIN_1ROWTHT"))
    )
    (comp (ref "Z_MOTOR_2")
      (value "4PIN_1ROWTHT")
      (footprint "eagle-import:4PIN_1ROW_2.54_THT")
      (libsource (lib "eagle-import") (part "4PIN_1ROWTHT"))
    )
  )
  (nets
    (net (code "1") (name "+5V") (class "Default")
      (node (ref "AUX-1") (pin "1") (pinfunction "1_1") (pintype "passive"))
      (node (ref "AUX-1") (pin "2") (pinfunction "2_2") (pintype "passive"))
      (node (ref "AUX-2") (pin "1") (pinfunction "1_1") (pintype "passive"))
      (node (ref "AUX-3") (pin "1") (pinfunction "1_1") (pintype "passive"))
      (node (ref "AUX-4") (pin "1") (pinfunction "1_1") (pintype "passive"))
      (node (ref "C1") (pin "2") (pinfunction "2_2") (pintype "passive"))
      (node (ref "C2") (pin "2") (pinfunction "2_2") (pintype "passive"))
      (node (ref "C22") (pin "1") (pinfunction "1_1") (pintype "passive"))
      (node (ref "C3") (pin "1") (pinfunction "1_1") (pintype "passive"))
      (node (ref "C30") (pin "1") (pinfunction "1_1") (pintype "passive"))
      (node (ref "C38") (pin "1") (pinfunction "1_1") (pintype "passive"))
      (node (ref "C39") (pin "1") (pinfunction "1_1") (pintype "passive"))
      (node (ref "C40") (pin "2") (pinfunction "2_2") (pintype "passive"))
      (node (ref "C41") (pin "1") (pinfunction "1_1") (pintype "passive"))
      (node (ref "C44") (pin "2") (pinfunction "2_2") (pintype "passive"))
      (node (ref "C45") (pin "2") (pinfunction "2_2") (pintype "passive"))
      (node (ref "C46") (pin "2") (pinfunction "2_2") (pintype "passive"))
      (node (ref "C47") (pin "2") (pinfunction "2_2") (pintype "passive"))
      (node (ref "C48") (pin "2") (pinfunction "2_2") (pintype "passive"))
      (node (ref "C49") (pin "2") (pinfunction "2_2") (pintype "passive"))
      (node (ref "C5") (pin "1") (pinfunction "1_1") (pintype "passive"))
      (node (ref "E0_ENDSTOP") (pin "2") (pinfunction "2_2") (pintype "passive"))
      (node (ref "E0_ENDSTOP") (pin "4") (pinfunction "4_4") (pintype "passive"))
      (node (ref "I2C") (pin "1") (pinfunction "1_1") (pintype "passive"))
      (node (ref "IC1") (pin "8") (pinfunction "VCC_8") (pintype "bidirectional"))
      (node (ref "IC2") (pin "8") (pinfunction "VCC_8") (pintype "bidirectional"))
      (node (ref "IC6") (pin "8") (pinfunction "VCC_8") (pintype "bidirectional"))
      (node (ref "R1") (pin "2") (pinfunction "2_2") (pintype "passive"))
      (node (ref "R19") (pin "2") (pinfunction "2_2") (pintype "passive"))
      (node (ref "R2") (pin "2") (pinfunction "2_2") (pintype "passive"))
      (node (ref "R20") (pin "2") (pinfunction "2_2") (pintype "passive"))
      (node (ref "R3") (pin "2") (pinfunction "2_2") (pintype "passive"))
      (node (ref "R33") (pin "1") (pinfunction "1_1") (pintype "passive"))
      (node (ref "R34") (pin "1") (pinfunction "1_1") (pintype "passive"))
      (node (ref "SERV_SUPPLY") (pin "1") (pinfunction "1_1") (pintype "passive"))
      (node (ref "SERV_SUPPLY") (pin "3") (pinfunction "3_3") (pintype "passive"))
      (node (ref "SERV_SUPPLY") (pin "5") (pinfunction "5_5") (pintype "passive"))
      (node (ref "SERV_SUPPLY") (pin "7") (pinfunction "7_7") (pintype "passive"))
      (node (ref "SHIELD") (pin "5V@0") (pinfunction "5V_5V@0") (pintype "bidirectional"))
      (node (ref "SHIELD") (pin "5V@1") (pinfunction "5V_5V@1") (pintype "bidirectional"))
      (node (ref "SHIELD") (pin "5V@2") (pinfunction "5V_5V@2") (pintype "bidirectional"))
      (node (ref "TMC1") (pin "10") (pinfunction "VCC_IO_10") (pintype "bidirectional"))
      (node (ref "TMC2") (pin "10") (pinfunction "VCC_IO_10") (pintype "bidirectional"))
      (node (ref "TMC3") (pin "10") (pinfunction "VCC_IO_10") (pintype "bidirectional"))
      (node (ref "TMC5130") (pin "10") (pinfunction "VCC_IO_10") (pintype "bidirectional"))
      (node (ref "XTAL") (pin "1") (pinfunction "E/D_1") (pintype "input"))
      (node (ref "XTAL") (pin "4") (pinfunction "VCC_4") (pintype "power_in"))
      (node (ref "X_ENDSTOP") (pin "2") (pinfunction "2_2") (pintype "passive"))
      (node (ref "X_ENDSTOP") (pin "4") (pinfunction "4_4") (pintype "passive"))
      (node (ref "Y_ENDSTOP") (pin "2") (pinfunction "2_2") (pintype "passive"))
      (node (ref "Y_ENDSTOP") (pin "4") (pinfunction "4_4") (pintype "passive"))
      (node (ref "Z_ENDSTOP") (pin "2") (pinfunction "2_2") (pintype "passive"))
      (node (ref "Z_ENDSTOP") (pin "4") (pinfunction "4_4") (pintype "passive"))
    )
    (net (code "2") (name "A3") (class "Default")
      (node (ref "AUX-1") (pin "5") (pinfunction "5_5") (pintype "passive"))
      (node (ref "SHIELD") (pin "A3") (pinfunction "A3_A3") (pintype "bidirectional"))
    )
    (net (code "3") (name "A4") (class "Default")
      (node (ref "AUX-1") (pin "7") (pinfunction "7_7") (pintype "passive"))
      (node (ref "SHIELD") (pin "A4") (pinfunction "A4_A4") (pintype "bidirectional"))
    )
    (net (code "4") (name "A5") (class "Default")
      (node (ref "AUX-2") (pin "3") (pinfunction "3_3") (pintype "passive"))
      (node (ref "SHIELD") (pin "A5") (pinfunction "A5_A5") (pintype "bidirectional"))
    )
    (net (code "5") (name "A9") (class "Default")
      (node (ref "AUX-2") (pin "4") (pinfunction "4_4") (pintype "passive"))
      (node (ref "SHIELD") (pin "A9") (pinfunction "A9_A9") (pintype "bidirectional"))
    )
    (net (code "6") (name "A10") (class "Default")
      (node (ref "AUX-2") (pin "5") (pinfunction "5_5") (pintype "passive"))
      (node (ref "SHIELD") (pin "A10") (pinfunction "A10_A10") (pintype "bidirectional"))
    )
    (net (code "7") (name "A11") (class "Default")
      (node (ref "AUX-2") (pin "10") (pinfunction "10_10") (pintype "passive"))
      (node (ref "SHIELD") (pin "A11") (pinfunction "A11_A11") (pintype "bidirectional"))
    )
    (net (code "8") (name "A12") (class "Default")
      (node (ref "AUX-2") (pin "9") (pinfunction "9_9") (pintype "passive"))
      (node (ref "SHIELD") (pin "A12") (pinfunction "A12_A12") (pintype "bidirectional"))
    )
    (net (code "9") (name "CLK") (class "Default")
      (node (ref "TMC1") (pin "2") (pinfunction "CLK_2") (pintype "bidirectional"))
      (node (ref "TMC2") (pin "2") (pinfunction "CLK_2") (pintype "bidirectional"))
      (node (ref "TMC3") (pin "2") (pinfunction "CLK_2") (pintype "bidirectional"))
      (node (ref "TMC5130") (pin "2") (pinfunction "CLK_2") (pintype "bidirectional"))
      (node (ref "XTAL") (pin "3") (pinfunction "OUT_3") (pintype "output"))
    )
    (net (code "10") (name "CS_E0") (class "Default")
      (node (ref "SHIELD") (pin "47") (pinfunction "47_47") (pintype "bidirectional"))
      (node (ref "TMC3") (pin "3") (pinfunction "CSN_CFG3_3") (pintype "bidirectional"))
    )
    (net (code "11") (name "CS_X") (class "Default")
      (node (ref "SHIELD") (pin "46") (pinfunction "46_46") (pintype "bidirectional"))
      (node (ref "TMC5130") (pin "3") (pinfunction "CSN_CFG3_3") (pintype "bidirectional"))
    )
    (net (code "12") (name "CS_Y") (class "Default")
      (node (ref "SHIELD") (pin "49") (pinfunction "49_49") (pintype "bidirectional"))
      (node (ref "TMC1") (pin "3") (pinfunction "CSN_CFG3_3") (pintype "bidirectional"))
    )
    (net (code "13") (name "CS_Z") (class "Default")
      (node (ref "SHIELD") (pin "48") (pinfunction "48_48") (pintype "bidirectional"))
      (node (ref "TMC2") (pin "3") (pinfunction "CSN_CFG3_3") (pintype "bidirectional"))
    )
    (net (code "14") (name "D0") (class "Default")
      (node (ref "AUX-1") (pin "8") (pinfunction "8_8") (pintype "passive"))
      (node (ref "SHIELD") (pin "0") (pinfunction "0(RX0)_0") (pintype "bidirectional"))
    )
    (net (code "15") (name "D1") (class "Default")
      (node (ref "AUX-1") (pin "6") (pinfunction "6_6") (pintype "passive"))
      (node (ref "SHIELD") (pin "1") (pinfunction "1(TX0)_1") (pintype "bidirectional"))
    )
    (net (code "16") (name "D4") (class "Default")
      (node (ref "SERVO") (pin "4") (pinfunction "4_4") (pintype "passive"))
      (node (ref "SHIELD") (pin "4") (pinfunction "4_4") (pintype "bidirectional"))
    )
    (net (code "17") (name "D5") (class "Default")
      (node (ref "SERVO") (pin "3") (pinfunction "3_3") (pintype "passive"))
      (node (ref "SHIELD") (pin "5") (pinfunction "5_5") (pintype "bidirectional"))
    )
    (net (code "18") (name "D6") (class "Default")
      (node (ref "SERVO") (pin "2") (pinfunction "2_2") (pintype "passive"))
      (node (ref "SHIELD") (pin "6") (pinfunction "6_6") (pintype "bidirectional"))
    )
    (net (code "19") (name "D11") (class "Default")
      (node (ref "SERVO") (pin "1") (pinfunction "1_1") (pintype "passive"))
      (node (ref "SHIELD") (pin "11") (pinfunction "11_11") (pintype "bidirectional"))
    )
    (net (code "20") (name "D16") (class "Default")
      (node (ref "AUX-4") (pin "18") (pinfunction "18_18") (pintype "passive"))
      (node (ref "SHIELD") (pin "16") (pinfunction "16(TX2)_16") (pintype "bidirectional"))
    )
    (net (code "21") (name "D17") (class "Default")
      (node (ref "AUX-4") (pin "17") (pinfunction "17_17") (pintype "passive"))
      (node (ref "SHIELD") (pin "17") (pinfunction "17(RX2)_17") (pintype "bidirectional"))
    )
    (net (code "22") (name "D23") (class "Default")
      (node (ref "AUX-4") (pin "16") (pinfunction "16_16") (pintype "passive"))
      (node (ref "SHIELD") (pin "23") (pinfunction "23_23") (pintype "bidirectional"))
    )
    (net (code "23") (name "D25") (class "Default")
      (node (ref "AUX-4") (pin "15") (pinfunction "15_15") (pintype "passive"))
      (node (ref "SHIELD") (pin "25") (pinfunction "25_25") (pintype "bidirectional"))
    )
    (net (code "24") (name "D27") (class "Default")
      (node (ref "AUX-4") (pin "14") (pinfunction "14_14") (pintype "passive"))
      (node (ref "SHIELD") (pin "27") (pinfunction "27_27") (pintype "bidirectional"))
    )
    (net (code "25") (name "D29") (class "Default")
      (node (ref "AUX-4") (pin "13") (pinfunction "13_13") (pintype "passive"))
      (node (ref "SHIELD") (pin "29") (pinfunction "29_29") (pintype "bidirectional"))
    )
    (net (code "26") (name "D31") (class "Default")
      (node (ref "AUX-4") (pin "12") (pinfunction "12_12") (pintype "passive"))
      (node (ref "SHIELD") (pin "31") (pinfunction "31_31") (pintype "bidirectional"))
    )
    (net (code "27") (name "D32") (class "Default")
      (node (ref "AUX-4") (pin "3") (pinfunction "3_3") (pintype "passive"))
      (node (ref "SHIELD") (pin "32") (pinfunction "32_32") (pintype "bidirectional"))
    )
    (net (code "28") (name "D33") (class "Default")
      (node (ref "AUX-4") (pin "11") (pinfunction "11_11") (pintype "passive"))
      (node (ref "SHIELD") (pin "33") (pinfunction "33_33") (pintype "bidirectional"))
    )
    (net (code "29") (name "D34") (class "Default")
      (node (ref "AUX-3") (pin "2") (pinfunction "2_2") (pintype "passive"))
      (node (ref "SHIELD") (pin "34") (pinfunction "34_34") (pintype "bidirectional"))
    )
    (net (code "30") (name "D35") (class "Default")
      (node (ref "AUX-4") (pin "10") (pinfunction "10_10") (pintype "passive"))
      (node (ref "SHIELD") (pin "35") (pinfunction "35_35") (pintype "bidirectional"))
    )
    (net (code "31") (name "D36") (class "Default")
      (node (ref "AUX-4") (pin "4") (pinfunction "4_4") (pintype "passive"))
      (node (ref "SHIELD") (pin "36") (pinfunction "36_36") (pintype "bidirectional"))
    )
    (net (code "32") (name "D37") (class "Default")
      (node (ref "AUX-4") (pin "9") (pinfunction "9_9") (pintype "passive"))
      (node (ref "SHIELD") (pin "37") (pinfunction "37_37") (pintype "bidirectional"))
    )
    (net (code "33") (name "D39") (class "Default")
      (node (ref "AUX-4") (pin "8") (pinfunction "8_8") (pintype "passive"))
      (node (ref "SHIELD") (pin "39") (pinfunction "39_39") (pintype "bidirectional"))
    )
    (net (code "34") (name "D40") (class "Default")
      (node (ref "AUX-2") (pin "6") (pinfunction "6_6") (pintype "passive"))
      (node (ref "SHIELD") (pin "40") (pinfunction "40_40") (pintype "bidirectional"))
    )
    (net (code "35") (name "D41") (class "Default")
      (node (ref "AUX-4") (pin "7") (pinfunction "7_7") (pintype "passive"))
      (node (ref "SHIELD") (pin "41") (pinfunction "41_41") (pintype "bidirectional"))
    )
    (net (code "36") (name "D42") (class "Default")
      (node (ref "AUX-2") (pin "8") (pinfunction "8_8") (pintype "passive"))
      (node (ref "SHIELD") (pin "42") (pinfunction "42_42") (pintype "bidirectional"))
    )
    (net (code "37") (name "D43") (class "Default")
      (node (ref "AUX-4") (pin "6") (pinfunction "6_6") (pintype "passive"))
      (node (ref "SHIELD") (pin "43") (pinfunction "43_43") (pintype "bidirectional"))
    )
    (net (code "38") (name "D44") (class "Default")
      (node (ref "AUX-2") (pin "7") (pinfunction "7_7") (pintype "passive"))
      (node (ref "SHIELD") (pin "44") (pinfunction "44_44") (pintype "bidirectional"))
    )
    (net (code "39") (name "D45") (class "Default")
      (node (ref "AUX-4") (pin "5") (pinfunction "5_5") (pintype "passive"))
      (node (ref "SHIELD") (pin "45") (pinfunction "45_45") (pintype "bidirectional"))
    )
    (net (code "40") (name "D53") (class "Default")
      (node (ref "AUX-3") (pin "6") (pinfunction "6_6") (pintype "passive"))
      (node (ref "SHIELD") (pin "53") (pinfunction "53_53") (pintype "bidirectional"))
    )
    (net (code "41") (name "DRV_EN_E0") (class "Default")
      (node (ref "SHIELD") (pin "24") (pinfunction "24_24") (pintype "bidirectional"))
      (node (ref "TMC3") (pin "29") (pinfunction "DRV_ENN_CFG6_29") (pintype "bidirectional"))
    )
    (net (code "42") (name "DRV_EN_X") (class "Default")
      (node (ref "SHIELD") (pin "38") (pinfunction "38_38") (pintype "bidirectional"))
      (node (ref "TMC5130") (pin "29") (pinfunction "DRV_ENN_CFG6_29") (pintype "bidirectional"))
    )
    (net (code "43") (name "DRV_EN_Y") (class "Default")
      (node (ref "SHIELD") (pin "A8") (pinfunction "A8_A8") (pintype "bidirectional"))
      (node (ref "TMC1") (pin "29") (pinfunction "DRV_ENN_CFG6_29") (pintype "bidirectional"))
    )
    (net (code "44") (name "DRV_EN_Z") (class "Default")
      (node (ref "SHIELD") (pin "A2") (pinfunction "A2_A2") (pintype "bidirectional"))
      (node (ref "TMC2") (pin "29") (pinfunction "DRV_ENN_CFG6_29") (pintype "bidirectional"))
    )
    (net (code "45") (name "ENDSTOP_E0_LEFT") (class "Default")
      (node (ref "C49") (pin "1") (pinfunction "1_1") (pintype "passive"))
      (node (ref "E0_ENDSTOP") (pin "5") (pinfunction "5_5") (pintype "passive"))
      (node (ref "R_PD12") (pin "2") (pinfunction "2_2") (pintype "passive"))
      (node (ref "TMC3") (pin "8") (pinfunction "REFL_STEP_8") (pintype "bidirectional"))
    )
    (net (code "46") (name "ENDSTOP_E0_RIGHT") (class "Default")
      (node (ref "C48") (pin "1") (pinfunction "1_1") (pintype "passive"))
      (node (ref "E0_ENDSTOP") (pin "1") (pinfunction "1_1") (pintype "passive"))
      (node (ref "R_PD13") (pin "2") (pinfunction "2_2") (pintype "passive"))
      (node (ref "TMC3") (pin "9") (pinfunction "REFR_DIR_9") (pintype "bidirectional"))
    )
    (net (code "47") (name "ENDSTOP_X_LEFT") (class "Default")
      (node (ref "C45") (pin "1") (pinfunction "1_1") (pintype "passive"))
      (node (ref "R_PD6") (pin "2") (pinfunction "2_2") (pintype "passive"))
      (node (ref "TMC5130") (pin "8") (pinfunction "REFL_STEP_8") (pintype "bidirectional"))
      (node (ref "X_ENDSTOP") (pin "5") (pinfunction "5_5") (pintype "passive"))
    )
    (net (code "48") (name "ENDSTOP_X_RIGHT") (class "Default")
      (node (ref "C44") (pin "1") (pinfunction "1_1") (pintype "passive"))
      (node (ref "R_PD7") (pin "2") (pinfunction "2_2") (pintype "passive"))
      (node (ref "TMC5130") (pin "9") (pinfunction "REFR_DIR_9") (pintype "bidirectional"))
      (node (ref "X_ENDSTOP") (pin "1") (pinfunction "1_1") (pintype "passive"))
    )
    (net (code "49") (name "ENDSTOP_Y_LEFT") (class "Default")
      (node (ref "C47") (pin "1") (pinfunction "1_1") (pintype "passive"))
      (node (ref "R_PD8") (pin "2") (pinfunction "2_2") (pintype "passive"))
      (node (ref "TMC1") (pin "8") (pinfunction "REFL_STEP_8") (pintype "bidirectional"))
      (node (ref "Y_ENDSTOP") (pin "5") (pinfunction "5_5") (pintype "passive"))
    )
    (net (code "50") (name "ENDSTOP_Y_RIGHT") (class "Default")
      (node (ref "C46") (pin "1") (pinfunction "1_1") (pintype "passive"))
      (node (ref "R_PD9") (pin "2") (pinfunction "2_2") (pintype "passive"))
      (node (ref "TMC1") (pin "9") (pinfunction "REFR_DIR_9") (pintype "bidirectional"))
      (node (ref "Y_ENDSTOP") (pin "1") (pinfunction "1_1") (pintype "passive"))
    )
    (net (code "51") (name "ENDSTOP_Z_LEFT") (class "Default")
      (node (ref "C1") (pin "1") (pinfunction "1_1") (pintype "passive"))
      (node (ref "R_PD10") (pin "2") (pinfunction "2_2") (pintype "passive"))
      (node (ref "TMC2") (pin "8") (pinfunction "REFL_STEP_8") (pintype "bidirectional"))
      (node (ref "Z_ENDSTOP") (pin "5") (pinfunction "5_5") (pintype "passive"))
    )
    (net (code "52") (name "ENDSTOP_Z_RIGHT") (class "Default")
      (node (ref "C40") (pin "1") (pinfunction "1_1") (pintype "passive"))
      (node (ref "R_PD11") (pin "2") (pinfunction "2_2") (pintype "passive"))
      (node (ref "TMC2") (pin "9") (pinfunction "REFR_DIR_9") (pintype "bidirectional"))
      (node (ref "Z_ENDSTOP") (pin "1") (pinfunction "1_1") (pintype "passive"))
    )
    (net (code "53") (name "FAN") (class "Default")
      (node (ref "IC2") (pin "1") (pinfunction "1A_1") (pintype "bidirectional"))
      (node (ref "IC2") (pin "3") (pinfunction "2A_3") (pintype "bidirectional"))
      (node (ref "IC2") (pin "6") (pinfunction "3A_6") (pintype "bidirectional"))
      (node (ref "R28") (pin "1") (pinfunction "1_1") (pintype "passive"))
      (node (ref "SHIELD") (pin "9") (pinfunction "9_9") (pintype "bidirectional"))
    )
    (net (code "54") (name "GND") (class "Default")
      (node (ref "AUX-1") (pin "3") (pinfunction "3_3") (pintype "passive"))
      (node (ref "AUX-1") (pin "4") (pinfunction "4_4") (pintype "passive"))
      (node (ref "AUX-2") (pin "2") (pinfunction "2_2") (pintype "passive"))
      (node (ref "AUX-3") (pin "7") (pinfunction "7_7") (pintype "passive"))
      (node (ref "AUX-4") (pin "2") (pinfunction "2_2") (pintype "passive"))
      (node (ref "C10") (pin "1") (pinfunction "1_1") (pintype "passive"))
      (node (ref "C11") (pin "2") (pinfunction "2_2") (pintype "passive"))
      (node (ref "C12") (pin "1") (pinfunction "1_1") (pintype "passive"))
      (node (ref "C13") (pin "1") (pinfunction "1_1") (pintype "passive"))
      (node (ref "C14") (pin "1") (pinfunction "1_1") (pintype "passive"))
      (node (ref "C15") (pin "1") (pinfunction "1_1") (pintype "passive"))
      (node (ref "C18") (pin "1") (pinfunction "1_1") (pintype "passive"))
      (node (ref "C19") (pin "2") (pinfunction "2_2") (pintype "passive"))
      (node (ref "C2") (pin "1") (pinfunction "1_1") (pintype "passive"))
      (node (ref "C20") (pin "1") (pinfunction "1_1") (pintype "passive"))
      (node (ref "C21") (pin "1") (pinfunction "1_1") (pintype "passive"))
      (node (ref "C22") (pin "2") (pinfunction "2_2") (pintype "passive"))
      (node (ref "C23") (pin "2") (pinfunction "2_2") (pintype "passive"))
      (node (ref "C26") (pin "1") (pinfunction "1_1") (pintype "passive"))
      (node (ref "C27") (pin "2") (pinfunction "2_2") (pintype "passive"))
      (node (ref "C28") (pin "1") (pinfunction "1_1") (pintype "passive"))
      (node (ref "C29") (pin "1") (pinfunction "1_1") (pintype "passive"))
      (node (ref "C3") (pin "2") (pinfunction "2_2") (pintype "passive"))
      (node (ref "C30") (pin "2") (pinfunction "2_2") (pintype "passive"))
      (node (ref "C31") (pin "2") (pinfunction "2_2") (pintype "passive"))
      (node (ref "C34") (pin "1") (pinfunction "1_1") (pintype "passive"))
      (node (ref "C35") (pin "2") (pinfunction "2_2") (pintype "passive"))
      (node (ref "C36") (pin "1") (pinfunction "1_1") (pintype "passive"))
      (node (ref "C37") (pin "1") (pinfunction "1_1") (pintype "passive"))
      (node (ref "C38") (pin "2") (pinfunction "2_2") (pintype "passive"))
      (node (ref "C39") (pin "2") (pinfunction "2_2") (pintype "passive"))
      (node (ref "C4") (pin "2") (pinfunction "2_2") (pintype "passive"))
      (node (ref "C41") (pin "2") (pinfunction "2_2") (pintype "passive"))
      (node (ref "C42") (pin "-") (pinfunction "-_-") (pintype "passive"))
      (node (ref "C43") (pin "-") (pinfunction "-_-") (pintype "passive"))
      (node (ref "C5") (pin "2") (pinfunction "2_2") (pintype "passive"))
      (node (ref "C6") (pin "2") (pinfunction "2_2") (pintype "passive"))
      (node (ref "C9") (pin "1") (pinfunction "1_1") (pintype "passive"))
      (node (ref "D2") (pin "A") (pinfunction "A_A") (pintype "bidirectional"))
      (node (ref "D4") (pin "A") (pinfunction "A_A") (pintype "bidirectional"))
      (node (ref "D5") (pin "A") (pinfunction "A_A") (pintype "bidirectional"))
      (node (ref "D6") (pin "A") (pinfunction "A_A") (pintype "bidirectional"))
      (node (ref "E0_ENDSTOP") (pin "3") (pinfunction "3_3") (pintype "passive"))
      (node (ref "I2C") (pin "2") (pinfunction "2_2") (pintype "passive"))
      (node (ref "IC1") (pin "4") (pinfunction "GND_4") (pintype "bidirectional"))
      (node (ref "IC2") (pin "4") (pinfunction "GND_4") (pintype "bidirectional"))
      (node (ref "IC6") (pin "4") (pinfunction "GND_4") (pintype "bidirectional"))
      (node (ref "MAIN_IN") (pin "P$1") (pinfunction "1_P$1") (pintype "bidirectional"))
      (node (ref "MAIN_IN") (pin "P$3") (pinfunction "3_P$3") (pintype "bidirectional"))
      (node (ref "R10") (pin "1") (pinfunction "1_1") (pintype "passive"))
      (node (ref "R11") (pin "1") (pinfunction "1_1") (pintype "passive"))
      (node (ref "R13") (pin "1") (pinfunction "1_1") (pintype "passive"))
      (node (ref "R14") (pin "1") (pinfunction "1_1") (pintype "passive"))
      (node (ref "R16") (pin "1") (pinfunction "1_1") (pintype "passive"))
      (node (ref "R17") (pin "1") (pinfunction "1_1") (pintype "passive"))
      (node (ref "R27") (pin "2") (pinfunction "2_2") (pintype "passive"))
      (node (ref "R28") (pin "2") (pinfunction "2_2") (pintype "passive"))
      (node (ref "R29") (pin "2") (pinfunction "2_2") (pintype "passive"))
      (node (ref "R5") (pin "1") (pinfunction "1_1") (pintype "passive"))
      (node (ref "R7") (pin "1") (pinfunction "1_1") (pintype "passive"))
      (node (ref "RL2") (pin "1") (pinfunction "1_1") (pintype "passive"))
      (node (ref "RL3") (pin "1") (pinfunction "1_1") (pintype "passive"))
      (node (ref "R_PD10") (pin "1") (pinfunction "1_1") (pintype "passive"))
      (node (ref "R_PD11") (pin "1") (pinfunction "1_1") (pintype "passive"))
      (node (ref "R_PD12") (pin "1") (pinfunction "1_1") (pintype "passive"))
      (node (ref "R_PD13") (pin "1") (pinfunction "1_1") (pintype "passive"))
      (node (ref "R_PD6") (pin "1") (pinfunction "1_1") (pintype "passive"))
      (node (ref "R_PD7") (pin "1") (pinfunction "1_1") (pintype "passive"))
      (node (ref "R_PD8") (pin "1") (pinfunction "1_1") (pintype "passive"))
      (node (ref "R_PD9") (pin "1") (pinfunction "1_1") (pintype "passive"))
      (node (ref "S1") (pin "1") (pinfunction "S_1") (pintype "passive"))
      (node (ref "S1") (pin "2") (pinfunction "S1_2") (pintype "passive"))
      (node (ref "SERV_SUPPLY") (pin "2") (pinfunction "2_2") (pintype "passive"))
      (node (ref "SERV_SUPPLY") (pin "4") (pinfunction "4_4") (pintype "passive"))
      (node (ref "SERV_SUPPLY") (pin "6") (pinfunction "6_6") (pintype "passive"))
      (node (ref "SERV_SUPPLY") (pin "8") (pinfunction "8_8") (pintype "passive"))
      (node (ref "SHIELD") (pin "GND@0") (pinfunction "GND_GND@0") (pintype "bidirectional"))
      (node (ref "SHIELD") (pin "GND@1") (pinfunction "GND_GND@1") (pintype "bidirectional"))
      (node (ref "SHIELD") (pin "GND@2") (pinfunction "GND_GND@2") (pintype "bidirectional"))
      (node (ref "SHIELD") (pin "GND@3") (pinfunction "GND_GND@3") (pintype "bidirectional"))
      (node (ref "SHIELD") (pin "GND@4") (pinfunction "GND_GND@4") (pintype "bidirectional"))
      (node (ref "T1") (pin "1") (pinfunction "1_1") (pintype "bidirectional"))
      (node (ref "T1") (pin "2") (pinfunction "2_2") (pintype "bidirectional"))
      (node (ref "T1") (pin "3") (pinfunction "3_3") (pintype "bidirectional"))
      (node (ref "T2") (pin "S0") (pinfunction "S_S0") (pintype "passive"))
      (node (ref "T2") (pin "S1") (pinfunction "S_S1") (pintype "passive"))
      (node (ref "T2") (pin "S2") (pinfunction "S_S2") (pintype "passive"))
      (node (ref "T7") (pin "1") (pinfunction "1_1") (pintype "bidirectional"))
      (node (ref "T7") (pin "2") (pinfunction "2_2") (pintype "bidirectional"))
      (node (ref "T7") (pin "3") (pinfunction "3_3") (pintype "bidirectional"))
      (node (ref "THERM0") (pin "1") (pinfunction "1_1") (pintype "bidirectional"))
      (node (ref "THERM1") (pin "1") (pinfunction "1_1") (pintype "bidirectional"))
      (node (ref "THERM2") (pin "1") (pinfunction "1_1") (pintype "bidirectional"))
      (node (ref "TMC1") (pin "1") (pinfunction "TST_MODE_1") (pintype "bidirectional"))
      (node (ref "TMC1") (pin "11") (pinfunction "SD_MODE_11") (pintype "bidirectional"))
      (node (ref "TMC1") (pin "13") (pinfunction "GNDP_13") (pintype "bidirectional"))
      (node (ref "TMC1") (pin "23") (pinfunction "ENCN_DCO_23") (pintype "bidirectional"))
      (node (ref "TMC1") (pin "31") (pinfunction "GND_31") (pintype "bidirectional"))
      (node (ref "TMC1") (pin "32") (pinfunction "GNDA_32") (pintype "bidirectional"))
      (node (ref "TMC1") (pin "36") (pinfunction "GND_36") (pintype "bidirectional"))
      (node (ref "TMC1") (pin "48") (pinfunction "GNDP_48") (pintype "bidirectional"))
      (node (ref "TMC1") (pin "6") (pinfunction "GND_6") (pintype "bidirectional"))
      (node (ref "TMC1") (pin "PAD") (pinfunction "GND_PAD_PAD") (pintype "bidirectional"))
      (node (ref "TMC2") (pin "1") (pinfunction "TST_MODE_1") (pintype "bidirectional"))
      (node (ref "TMC2") (pin "11") (pinfunction "SD_MODE_11") (pintype "bidirectional"))
      (node (ref "TMC2") (pin "13") (pinfunction "GNDP_13") (pintype "bidirectional"))
      (node (ref "TMC2") (pin "23") (pinfunction "ENCN_DCO_23") (pintype "bidirectional"))
      (node (ref "TMC2") (pin "31") (pinfunction "GND_31") (pintype "bidirectional"))
      (node (ref "TMC2") (pin "32") (pinfunction "GNDA_32") (pintype "bidirectional"))
      (node (ref "TMC2") (pin "36") (pinfunction "GND_36") (pintype "bidirectional"))
      (node (ref "TMC2") (pin "48") (pinfunction "GNDP_48") (pintype "bidirectional"))
      (node (ref "TMC2") (pin "6") (pinfunction "GND_6") (pintype "bidirectional"))
      (node (ref "TMC2") (pin "PAD") (pinfunction "GND_PAD_PAD") (pintype "bidirectional"))
      (node (ref "TMC3") (pin "1") (pinfunction "TST_MODE_1") (pintype "bidirectional"))
      (node (ref "TMC3") (pin "11") (pinfunction "SD_MODE_11") (pintype "bidirectional"))
      (node (ref "TMC3") (pin "13") (pinfunction "GNDP_13") (pintype "bidirectional"))
      (node (ref "TMC3") (pin "23") (pinfunction "ENCN_DCO_23") (pintype "bidirectional"))
      (node (ref "TMC3") (pin "31") (pinfunction "GND_31") (pintype "bidirectional"))
      (node (ref "TMC3") (pin "32") (pinfunction "GNDA_32") (pintype "bidirectional"))
      (node (ref "TMC3") (pin "36") (pinfunction "GND_36") (pintype "bidirectional"))
      (node (ref "TMC3") (pin "48") (pinfunction "GNDP_48") (pintype "bidirectional"))
      (node (ref "TMC3") (pin "6") (pinfunction "GND_6") (pintype "bidirectional"))
      (node (ref "TMC3") (pin "PAD") (pinfunction "GND_PAD_PAD") (pintype "bidirectional"))
      (node (ref "TMC5130") (pin "1") (pinfunction "TST_MODE_1") (pintype "bidirectional"))
      (node (ref "TMC5130") (pin "11") (pinfunction "SD_MODE_11") (pintype "bidirectional"))
      (node (ref "TMC5130") (pin "13") (pinfunction "GNDP_13") (pintype "bidirectional"))
      (node (ref "TMC5130") (pin "23") (pinfunction "ENCN_DCO_23") (pintype "bidirectional"))
      (node (ref "TMC5130") (pin "31") (pinfunction "GND_31") (pintype "bidirectional"))
      (node (ref "TMC5130") (pin "32") (pinfunction "GNDA_32") (pintype "bidirectional"))
      (node (ref "TMC5130") (pin "36") (pinfunction "GND_36") (pintype "bidirectional"))
      (node (ref "TMC5130") (pin "48") (pinfunction "GNDP_48") (pintype "bidirectional"))
      (node (ref "TMC5130") (pin "6") (pinfunction "GND_6") (pintype "bidirectional"))
      (node (ref "TMC5130") (pin "PAD") (pinfunction "GND_PAD_PAD") (pintype "bidirectional"))
      (node (ref "VM0") (pin "1") (pinfunction "1_1") (pintype "bidirectional"))
      (node (ref "VM1") (pin "1") (pinfunction "1_1") (pintype "bidirectional"))
      (node (ref "XTAL") (pin "2") (pinfunction "GND_2") (pintype "power_in"))
      (node (ref "X_ENDSTOP") (pin "3") (pinfunction "3_3") (pintype "passive"))
      (node (ref "Y_ENDSTOP") (pin "3") (pinfunction "3_3") (pintype "passive"))
      (node (ref "Z_ENDSTOP") (pin "3") (pinfunction "3_3") (pintype "passive"))
    )
    (net (code "55") (name "HEATBED") (class "Default")
      (node (ref "IC6") (pin "1") (pinfunction "1A_1") (pintype "bidirectional"))
      (node (ref "IC6") (pin "3") (pinfunction "2A_3") (pintype "bidirectional"))
      (node (ref "IC6") (pin "6") (pinfunction "3A_6") (pintype "bidirectional"))
      (node (ref "R27") (pin "1") (pinfunction "1_1") (pintype "passive"))
      (node (ref "SHIELD") (pin "8") (pinfunction "8_8") (pintype "bidirectional"))
    )
    (net (code "56") (name "HEATBED_POWER") (class "Default")
      (node (ref "F2") (pin "P$1") (pinfunction "1_P$1") (pintype "passive"))
      (node (ref "MAIN_IN") (pin "P$4") (pinfunction "4_P$4") (pintype "bidirectional"))
    )
    (net (code "57") (name "HEAT_E0") (class "Default")
      (node (ref "IC1") (pin "1") (pinfunction "1A_1") (pintype "bidirectional"))
      (node (ref "IC1") (pin "3") (pinfunction "2A_3") (pintype "bidirectional"))
      (node (ref "IC1") (pin "6") (pinfunction "3A_6") (pintype "bidirectional"))
      (node (ref "R29") (pin "1") (pinfunction "1_1") (pintype "passive"))
      (node (ref "SHIELD") (pin "10") (pinfunction "10_10") (pintype "bidirectional"))
    )
    (net (code "58") (name "INTERRUPT") (class "Default")
      (node (ref "R33") (pin "2") (pinfunction "2_2") (pintype "passive"))
      (node (ref "SHIELD") (pin "2") (pinfunction "2_2") (pintype "bidirectional"))
      (node (ref "TMC1") (pin "26") (pinfunction "SWN_DIAG0_26") (pintype "bidirectional"))
      (node (ref "TMC2") (pin "26") (pinfunction "SWN_DIAG0_26") (pintype "bidirectional"))
      (node (ref "TMC3") (pin "26") (pinfunction "SWN_DIAG0_26") (pintype "bidirectional"))
      (node (ref "TMC5130") (pin "26") (pinfunction "SWN_DIAG0_26") (pintype "bidirectional"))
    )
    (net (code "59") (name "M1A1_E0") (class "Default")
      (node (ref "E0_MOTOR") (pin "1") (pinfunction "1_1") (pintype "passive"))
      (node (ref "TMC3") (pin "46") (pinfunction "OA1_46") (pintype "bidirectional"))
    )
    (net (code "60") (name "M1A1_X") (class "Default")
      (node (ref "TMC5130") (pin "46") (pinfunction "OA1_46") (pintype "bidirectional"))
      (node (ref "X_MOTOR") (pin "1") (pinfunction "1_1") (pintype "passive"))
    )
    (net (code "61") (name "M1A1_Y") (class "Default")
      (node (ref "TMC1") (pin "46") (pinfunction "OA1_46") (pintype "bidirectional"))
      (node (ref "Y_MOTOR") (pin "1") (pinfunction "1_1") (pintype "passive"))
    )
    (net (code "62") (name "M1A1_Z") (class "Default")
      (node (ref "TMC2") (pin "46") (pinfunction "OA1_46") (pintype "bidirectional"))
      (node (ref "Z_MOTOR_1") (pin "1") (pinfunction "1_1") (pintype "passive"))
    )
    (net (code "63") (name "M1A2_E0") (class "Default")
      (node (ref "E0_MOTOR") (pin "2") (pinfunction "2_2") (pintype "passive"))
      (node (ref "TMC3") (pin "42") (pinfunction "OA2_42") (pintype "bidirectional"))
    )
    (net (code "64") (name "M1A2_X") (class "Default")
      (node (ref "TMC5130") (pin "42") (pinfunction "OA2_42") (pintype "bidirectional"))
      (node (ref "X_MOTOR") (pin "2") (pinfunction "2_2") (pintype "passive"))
    )
    (net (code "65") (name "M1A2_Y") (class "Default")
      (node (ref "TMC1") (pin "42") (pinfunction "OA2_42") (pintype "bidirectional"))
      (node (ref "Y_MOTOR") (pin "2") (pinfunction "2_2") (pintype "passive"))
    )
    (net (code "66") (name "M1A2_Z") (class "Default")
      (node (ref "TMC2") (pin "42") (pinfunction "OA2_42") (pintype "bidirectional"))
      (node (ref "Z_MOTOR_2") (pin "2") (pinfunction "2_2") (pintype "passive"))
    )
    (net (code "67") (name "M1B1_E0") (class "Default")
      (node (ref "E0_MOTOR") (pin "3") (pinfunction "3_3") (pintype "passive"))
      (node (ref "TMC3") (pin "15") (pinfunction "OB1_15") (pintype "bidirectional"))
    )
    (net (code "68") (name "M1B1_X") (class "Default")
      (node (ref "TMC5130") (pin "15") (pinfunction "OB1_15") (pintype "bidirectional"))
      (node (ref "X_MOTOR") (pin "3") (pinfunction "3_3") (pintype "passive"))
    )
    (net (code "69") (name "M1B1_Y") (class "Default")
      (node (ref "TMC1") (pin "15") (pinfunction "OB1_15") (pintype "bidirectional"))
      (node (ref "Y_MOTOR") (pin "3") (pinfunction "3_3") (pintype "passive"))
    )
    (net (code "70") (name "M1B1_Z") (class "Default")
      (node (ref "TMC2") (pin "15") (pinfunction "OB1_15") (pintype "bidirectional"))
      (node (ref "Z_MOTOR_1") (pin "3") (pinfunction "3_3") (pintype "passive"))
    )
    (net (code "71") (name "M1B2_E0") (class "Default")
      (node (ref "E0_MOTOR") (pin "4") (pinfunction "4_4") (pintype "passive"))
      (node (ref "TMC3") (pin "19") (pinfunction "OB2_19") (pintype "bidirectional"))
    )
    (net (code "72") (name "M1B2_X") (class "Default")
      (node (ref "TMC5130") (pin "19") (pinfunction "OB2_19") (pintype "bidirectional"))
      (node (ref "X_MOTOR") (pin "4") (pinfunction "4_4") (pintype "passive"))
    )
    (net (code "73") (name "M1B2_Y") (class "Default")
      (node (ref "TMC1") (pin "19") (pinfunction "OB2_19") (pintype "bidirectional"))
      (node (ref "Y_MOTOR") (pin "4") (pinfunction "4_4") (pintype "passive"))
    )
    (net (code "74") (name "M1B2_Z") (class "Default")
      (node (ref "TMC2") (pin "19") (pinfunction "OB2_19") (pintype "bidirectional"))
      (node (ref "Z_MOTOR_2") (pin "4") (pinfunction "4_4") (pintype "passive"))
    )
    (net (code "75") (name "MAIN_POWER") (class "Default")
      (node (ref "F1") (pin "P$1") (pinfunction "1_P$1") (pintype "passive"))
      (node (ref "MAIN_IN") (pin "P$2") (pinfunction "2_P$2") (pintype "bidirectional"))
    )
    (net (code "76") (name "MISO") (class "Default")
      (node (ref "AUX-3") (pin "3") (pinfunction "3_3") (pintype "passive"))
      (node (ref "SHIELD") (pin "50") (pinfunction "50_50") (pintype "bidirectional"))
      (node (ref "TMC1") (pin "7") (pinfunction "SDO_NAO_CFG0_7") (pintype "bidirectional"))
      (node (ref "TMC2") (pin "7") (pinfunction "SDO_NAO_CFG0_7") (pintype "bidirectional"))
      (node (ref "TMC3") (pin "7") (pinfunction "SDO_NAO_CFG0_7") (pintype "bidirectional"))
      (node (ref "TMC5130") (pin "7") (pinfunction "SDO_NAO_CFG0_7") (pintype "bidirectional"))
    )
    (net (code "77") (name "MOSI") (class "Default")
      (node (ref "AUX-3") (pin "4") (pinfunction "4_4") (pintype "passive"))
      (node (ref "SHIELD") (pin "51") (pinfunction "51_51") (pintype "bidirectional"))
      (node (ref "TMC1") (pin "5") (pinfunction "SDI_NAI_CFG1_5") (pintype "bidirectional"))
      (node (ref "TMC2") (pin "5") (pinfunction "SDI_NAI_CFG1_5") (pintype "bidirectional"))
      (node (ref "TMC3") (pin "5") (pinfunction "SDI_NAI_CFG1_5") (pintype "bidirectional"))
      (node (ref "TMC5130") (pin "5") (pinfunction "SDI_NAI_CFG1_5") (pintype "bidirectional"))
    )
    (net (code "78") (name "Net-(EX_0-1)") (class "Default")
      (node (ref "D_HB1") (pin "A") (pinfunction "A_A") (pintype "bidirectional"))
      (node (ref "EX_0") (pin "P$1") (pinfunction "1_P$1") (pintype "bidirectional"))
      (node (ref "LED1") (pin "C") (pinfunction "C_C") (pintype "passive"))
      (node (ref "T1") (pin "5") (pinfunction "5_5") (pintype "bidirectional"))
      (node (ref "T1") (pin "6") (pinfunction "6_6") (pintype "bidirectional"))
      (node (ref "T1") (pin "7") (pinfunction "7_7") (pintype "bidirectional"))
      (node (ref "T1") (pin "8") (pinfunction "8_8") (pintype "bidirectional"))
      (node (ref "T1") (pin "9") (pinfunction "9_9") (pintype "bidirectional"))
    )
    (net (code "79") (name "Net-(FAN-1)") (class "Default")
      (node (ref "D_HB2") (pin "A") (pinfunction "A_A") (pintype "bidirectional"))
      (node (ref "FAN") (pin "P$1") (pinfunction "1_P$1") (pintype "bidirectional"))
      (node (ref "LED4") (pin "C") (pinfunction "C_C") (pintype "passive"))
      (node (ref "T2") (pin "D0") (pinfunction "D_D0") (pintype "passive"))
      (node (ref "T2") (pin "D1") (pinfunction "D_D1") (pintype "passive"))
      (node (ref "T2") (pin "D2") (pinfunction "D_D2") (pintype "passive"))
      (node (ref "T2") (pin "D3") (pinfunction "D_D3") (pintype "passive"))
      (node (ref "T2") (pin "D4") (pinfunction "D_D4") (pintype "passive"))
      (node (ref "T2") (pin "D5") (pinfunction "D_D5") (pintype "passive"))
      (node (ref "T2") (pin "D6") (pinfunction "D_D6") (pintype "passive"))
    )
    (net (code "80") (name "Net-(HEATBED-1)") (class "Default")
      (node (ref "D_HB") (pin "A") (pinfunction "A_A") (pintype "bidirectional"))
      (node (ref "HEATBED") (pin "P$1") (pinfunction "1_P$1") (pintype "bidirectional"))
      (node (ref "LED6") (pin "C") (pinfunction "C_C") (pintype "passive"))
      (node (ref "T7") (pin "5") (pinfunction "5_5") (pintype "bidirectional"))
      (node (ref "T7") (pin "6") (pinfunction "6_6") (pintype "bidirectional"))
      (node (ref "T7") (pin "7") (pinfunction "7_7") (pintype "bidirectional"))
      (node (ref "T7") (pin "8") (pinfunction "8_8") (pintype "bidirectional"))
      (node (ref "T7") (pin "9") (pinfunction "9_9") (pintype "bidirectional"))
    )
    (net (code "81") (name "Net-(IC1-1Y)") (class "Default")
      (node (ref "IC1") (pin "7") (pinfunction "1Y_7") (pintype "bidirectional"))
      (node (ref "R8") (pin "2") (pinfunction "2_2") (pintype "passive"))
    )
    (net (code "82") (name "Net-(IC1-2Y)") (class "Default")
      (node (ref "IC1") (pin "5") (pinfunction "2Y_5") (pintype "bidirectional"))
      (node (ref "R4") (pin "2") (pinfunction "2_2") (pintype "passive"))
    )
    (net (code "83") (name "Net-(IC1-3Y)") (class "Default")
      (node (ref "IC1") (pin "2") (pinfunction "3Y_2") (pintype "bidirectional"))
      (node (ref "R9") (pin "2") (pinfunction "2_2") (pintype "passive"))
    )
    (net (code "84") (name "Net-(IC2-1Y)") (class "Default")
      (node (ref "IC2") (pin "7") (pinfunction "1Y_7") (pintype "bidirectional"))
      (node (ref "R23") (pin "2") (pinfunction "2_2") (pintype "passive"))
    )
    (net (code "85") (name "Net-(IC2-2Y)") (class "Default")
      (node (ref "IC2") (pin "5") (pinfunction "2Y_5") (pintype "bidirectional"))
      (node (ref "R22") (pin "2") (pinfunction "2_2") (pintype "passive"))
    )
    (net (code "86") (name "Net-(IC2-3Y)") (class "Default")
      (node (ref "IC2") (pin "2") (pinfunction "3Y_2") (pintype "bidirectional"))
      (node (ref "R25") (pin "2") (pinfunction "2_2") (pintype "passive"))
    )
    (net (code "87") (name "Net-(IC6-1Y)") (class "Default")
      (node (ref "IC6") (pin "7") (pinfunction "1Y_7") (pintype "bidirectional"))
      (node (ref "R31") (pin "2") (pinfunction "2_2") (pintype "passive"))
    )
    (net (code "88") (name "Net-(IC6-2Y)") (class "Default")
      (node (ref "IC6") (pin "5") (pinfunction "2Y_5") (pintype "bidirectional"))
      (node (ref "R30") (pin "2") (pinfunction "2_2") (pintype "passive"))
    )
    (net (code "89") (name "Net-(IC6-3Y)") (class "Default")
      (node (ref "IC6") (pin "2") (pinfunction "3Y_2") (pintype "bidirectional"))
      (node (ref "R32") (pin "2") (pinfunction "2_2") (pintype "passive"))
    )
    (net (code "90") (name "Net-(LED1-PadA)") (class "Default")
      (node (ref "LED1") (pin "A") (pinfunction "A_A") (pintype "passive"))
      (node (ref "R21") (pin "1") (pinfunction "1_1") (pintype "passive"))
    )
    (net (code "91") (name "Net-(LED2-PadC)") (class "Default")
      (node (ref "LED2") (pin "C") (pinfunction "C_C") (pintype "passive"))
      (node (ref "RL2") (pin "2") (pinfunction "2_2") (pintype "passive"))
    )
    (net (code "92") (name "Net-(LED3-PadC)") (class "Default")
      (node (ref "LED3") (pin "C") (pinfunction "C_C") (pintype "passive"))
      (node (ref "RL3") (pin "2") (pinfunction "2_2") (pintype "passive"))
    )
    (net (code "93") (name "Net-(LED4-PadA)") (class "Default")
      (node (ref "LED4") (pin "A") (pinfunction "A_A") (pintype "passive"))
      (node (ref "R26") (pin "1") (pinfunction "1_1") (pintype "passive"))
    )
    (net (code "94") (name "Net-(LED6-PadA)") (class "Default")
      (node (ref "LED6") (pin "A") (pinfunction "A_A") (pintype "passive"))
      (node (ref "R24") (pin "1") (pinfunction "1_1") (pintype "passive"))
    )
    (net (code "95") (name "Net-(R4-Pad1)") (class "Default")
      (node (ref "R4") (pin "1") (pinfunction "1_1") (pintype "passive"))
      (node (ref "R8") (pin "1") (pinfunction "1_1") (pintype "passive"))
      (node (ref "R9") (pin "1") (pinfunction "1_1") (pintype "passive"))
      (node (ref "T1") (pin "4") (pinfunction "4_4") (pintype "bidirectional"))
    )
    (net (code "96") (name "Net-(R22-Pad1)") (class "Default")
      (node (ref "R22") (pin "1") (pinfunction "1_1") (pintype "passive"))
      (node (ref "R23") (pin "1") (pinfunction "1_1") (pintype "passive"))
      (node (ref "R25") (pin "1") (pinfunction "1_1") (pintype "passive"))
      (node (ref "T2") (pin "G") (pinfunction "G_G") (pintype "passive"))
    )
    (net (code "97") (name "Net-(R30-Pad1)") (class "Default")
      (node (ref "R30") (pin "1") (pinfunction "1_1") (pintype "passive"))
      (node (ref "R31") (pin "1") (pinfunction "1_1") (pintype "passive"))
      (node (ref "R32") (pin "1") (pinfunction "1_1") (pintype "passive"))
      (node (ref "T7") (pin "4") (pinfunction "4_4") (pintype "bidirectional"))
    )
    (net (code "98") (name "Net-(TMC1-5VOUT)") (class "Default")
      (node (ref "C4") (pin "1") (pinfunction "1_1") (pintype "passive"))
      (node (ref "R12") (pin "1") (pinfunction "1_1") (pintype "passive"))
      (node (ref "TMC1") (pin "33") (pinfunction "5VOUT_33") (pintype "bidirectional"))
    )
    (net (code "99") (name "Net-(TMC1-BRA)") (class "Default")
      (node (ref "R11") (pin "2") (pinfunction "2_2") (pintype "passive"))
      (node (ref "TMC1") (pin "44") (pinfunction "BRA_44") (pintype "bidirectional"))
    )
    (net (code "100") (name "Net-(TMC1-BRB)") (class "Default")
      (node (ref "R10") (pin "2") (pinfunction "2_2") (pintype "passive"))
      (node (ref "TMC1") (pin "17") (pinfunction "BRB_17") (pintype "bidirectional"))
    )
    (net (code "101") (name "Net-(TMC1-CPI)") (class "Default")
      (node (ref "C17") (pin "1") (pinfunction "1_1") (pintype "passive"))
      (node (ref "TMC1") (pin "37") (pinfunction "CPI_37") (pintype "bidirectional"))
    )
    (net (code "102") (name "Net-(TMC1-CPO)") (class "Default")
      (node (ref "C17") (pin "2") (pinfunction "2_2") (pintype "passive"))
      (node (ref "TMC1") (pin "35") (pinfunction "CPO_35") (pintype "bidirectional"))
    )
    (net (code "103") (name "Net-(TMC1-VCC)") (class "Default")
      (node (ref "C21") (pin "2") (pinfunction "2_2") (pintype "passive"))
      (node (ref "R12") (pin "2") (pinfunction "2_2") (pintype "passive"))
      (node (ref "TMC1") (pin "34") (pinfunction "VCC_34") (pintype "bidirectional"))
    )
    (net (code "104") (name "Net-(TMC1-VCP)") (class "Default")
      (node (ref "C16") (pin "2") (pinfunction "2_2") (pintype "passive"))
      (node (ref "TMC1") (pin "38") (pinfunction "VCP_38") (pintype "bidirectional"))
    )
    (net (code "105") (name "Net-(TMC2-5VOUT)") (class "Default")
      (node (ref "C23") (pin "1") (pinfunction "1_1") (pintype "passive"))
      (node (ref "R15") (pin "1") (pinfunction "1_1") (pintype "passive"))
      (node (ref "TMC2") (pin "33") (pinfunction "5VOUT_33") (pintype "bidirectional"))
    )
    (net (code "106") (name "Net-(TMC2-BRA)") (class "Default")
      (node (ref "R14") (pin "2") (pinfunction "2_2") (pintype "passive"))
      (node (ref "TMC2") (pin "44") (pinfunction "BRA_44") (pintype "bidirectional"))
    )
    (net (code "107") (name "Net-(TMC2-BRB)") (class "Default")
      (node (ref "R13") (pin "2") (pinfunction "2_2") (pintype "passive"))
      (node (ref "TMC2") (pin "17") (pinfunction "BRB_17") (pintype "bidirectional"))
    )
    (net (code "108") (name "Net-(TMC2-CPI)") (class "Default")
      (node (ref "C25") (pin "1") (pinfunction "1_1") (pintype "passive"))
      (node (ref "TMC2") (pin "37") (pinfunction "CPI_37") (pintype "bidirectional"))
    )
    (net (code "109") (name "Net-(TMC2-CPO)") (class "Default")
      (node (ref "C25") (pin "2") (pinfunction "2_2") (pintype "passive"))
      (node (ref "TMC2") (pin "35") (pinfunction "CPO_35") (pintype "bidirectional"))
    )
    (net (code "110") (name "Net-(TMC2-VCC)") (class "Default")
      (node (ref "C29") (pin "2") (pinfunction "2_2") (pintype "passive"))
      (node (ref "R15") (pin "2") (pinfunction "2_2") (pintype "passive"))
      (node (ref "TMC2") (pin "34") (pinfunction "VCC_34") (pintype "bidirectional"))
    )
    (net (code "111") (name "Net-(TMC2-VCP)") (class "Default")
      (node (ref "C24") (pin "2") (pinfunction "2_2") (pintype "passive"))
      (node (ref "TMC2") (pin "38") (pinfunction "VCP_38") (pintype "bidirectional"))
    )
    (net (code "112") (name "Net-(TMC3-5VOUT)") (class "Default")
      (node (ref "C31") (pin "1") (pinfunction "1_1") (pintype "passive"))
      (node (ref "R18") (pin "1") (pinfunction "1_1") (pintype "passive"))
      (node (ref "TMC3") (pin "33") (pinfunction "5VOUT_33") (pintype "bidirectional"))
    )
    (net (code "113") (name "Net-(TMC3-BRA)") (class "Default")
      (node (ref "R17") (pin "2") (pinfunction "2_2") (pintype "passive"))
      (node (ref "TMC3") (pin "44") (pinfunction "BRA_44") (pintype "bidirectional"))
    )
    (net (code "114") (name "Net-(TMC3-BRB)") (class "Default")
      (node (ref "R16") (pin "2") (pinfunction "2_2") (pintype "passive"))
      (node (ref "TMC3") (pin "17") (pinfunction "BRB_17") (pintype "bidirectional"))
    )
    (net (code "115") (name "Net-(TMC3-CPI)") (class "Default")
      (node (ref "C33") (pin "1") (pinfunction "1_1") (pintype "passive"))
      (node (ref "TMC3") (pin "37") (pinfunction "CPI_37") (pintype "bidirectional"))
    )
    (net (code "116") (name "Net-(TMC3-CPO)") (class "Default")
      (node (ref "C33") (pin "2") (pinfunction "2_2") (pintype "passive"))
      (node (ref "TMC3") (pin "35") (pinfunction "CPO_35") (pintype "bidirectional"))
    )
    (net (code "117") (name "Net-(TMC3-VCC)") (class "Default")
      (node (ref "C37") (pin "2") (pinfunction "2_2") (pintype "passive"))
      (node (ref "R18") (pin "2") (pinfunction "2_2") (pintype "passive"))
      (node (ref "TMC3") (pin "34") (pinfunction "VCC_34") (pintype "bidirectional"))
    )
    (net (code "118") (name "Net-(TMC3-VCP)") (class "Default")
      (node (ref "C32") (pin "2") (pinfunction "2_2") (pintype "passive"))
      (node (ref "TMC3") (pin "38") (pinfunction "VCP_38") (pintype "bidirectional"))
    )
    (net (code "119") (name "Net-(TMC5130-5VOUT)") (class "Default")
      (node (ref "C6") (pin "1") (pinfunction "1_1") (pintype "passive"))
      (node (ref "R6") (pin "1") (pinfunction "1_1") (pintype "passive"))
      (node (ref "TMC5130") (pin "33") (pinfunction "5VOUT_33") (pintype "bidirectional"))
    )
    (net (code "120") (name "Net-(TMC5130-BRA)") (class "Default")
      (node (ref "R5") (pin "2") (pinfunction "2_2") (pintype "passive"))
      (node (ref "TMC5130") (pin "44") (pinfunction "BRA_44") (pintype "bidirectional"))
    )
    (net (code "121") (name "Net-(TMC5130-BRB)") (class "Default")
      (node (ref "R7") (pin "2") (pinfunction "2_2") (pintype "passive"))
      (node (ref "TMC5130") (pin "17") (pinfunction "BRB_17") (pintype "bidirectional"))
    )
    (net (code "122") (name "Net-(TMC5130-CPI)") (class "Default")
      (node (ref "C8") (pin "1") (pinfunction "1_1") (pintype "passive"))
      (node (ref "TMC5130") (pin "37") (pinfunction "CPI_37") (pintype "bidirectional"))
    )
    (net (code "123") (name "Net-(TMC5130-CPO)") (class "Default")
      (node (ref "C8") (pin "2") (pinfunction "2_2") (pintype "passive"))
      (node (ref "TMC5130") (pin "35") (pinfunction "CPO_35") (pintype "bidirectional"))
    )
    (net (code "124") (name "Net-(TMC5130-VCC)") (class "Default")
      (node (ref "C9") (pin "2") (pinfunction "2_2") (pintype "passive"))
      (node (ref "R6") (pin "2") (pinfunction "2_2") (pintype "passive"))
      (node (ref "TMC5130") (pin "34") (pinfunction "VCC_34") (pintype "bidirectional"))
    )
    (net (code "125") (name "Net-(TMC5130-VCP)") (class "Default")
      (node (ref "C7") (pin "2") (pinfunction "2_2") (pintype "passive"))
      (node (ref "TMC5130") (pin "38") (pinfunction "VCP_38") (pintype "bidirectional"))
    )
    (net (code "126") (name "Net-(Z_MOTOR_1-Pad2)") (class "Default")
      (node (ref "Z_MOTOR_1") (pin "2") (pinfunction "2_2") (pintype "passive"))
      (node (ref "Z_MOTOR_2") (pin "1") (pinfunction "1_1") (pintype "passive"))
    )
    (net (code "127") (name "Net-(Z_MOTOR_1-Pad4)") (class "Default")
      (node (ref "Z_MOTOR_1") (pin "4") (pinfunction "4_4") (pintype "passive"))
      (node (ref "Z_MOTOR_2") (pin "3") (pinfunction "3_3") (pintype "passive"))
    )
    (net (code "128") (name "POSPULSE") (class "Default")
      (node (ref "R34") (pin "2") (pinfunction "2_2") (pintype "passive"))
      (node (ref "SHIELD") (pin "3") (pinfunction "3_3") (pintype "bidirectional"))
      (node (ref "TMC1") (pin "27") (pinfunction "SWP_DIAG1_27") (pintype "bidirectional"))
      (node (ref "TMC2") (pin "27") (pinfunction "SWP_DIAG1_27") (pintype "bidirectional"))
      (node (ref "TMC3") (pin "27") (pinfunction "SWP_DIAG1_27") (pintype "bidirectional"))
      (node (ref "TMC5130") (pin "27") (pinfunction "SWP_DIAG1_27") (pintype "bidirectional"))
    )
    (net (code "129") (name "RESET") (class "Default")
      (node (ref "S1") (pin "3") (pinfunction "P_3") (pintype "passive"))
      (node (ref "S1") (pin "4") (pinfunction "P1_4") (pintype "passive"))
      (node (ref "SHIELD") (pin "RESET") (pinfunction "RESET_RESET") (pintype "bidirectional"))
    )
    (net (code "130") (name "SCK") (class "Default")
      (node (ref "AUX-3") (pin "5") (pinfunction "5_5") (pintype "passive"))
      (node (ref "SHIELD") (pin "52") (pinfunction "52_52") (pintype "bidirectional"))
      (node (ref "TMC1") (pin "4") (pinfunction "SCK_CFG2_4") (pintype "bidirectional"))
      (node (ref "TMC2") (pin "4") (pinfunction "SCK_CFG2_4") (pintype "bidirectional"))
      (node (ref "TMC3") (pin "4") (pinfunction "SCK_CFG2_4") (pintype "bidirectional"))
      (node (ref "TMC5130") (pin "4") (pinfunction "SCK_CFG2_4") (pintype "bidirectional"))
    )
    (net (code "131") (name "SCL") (class "Default")
      (node (ref "I2C") (pin "4") (pinfunction "4_4") (pintype "passive"))
      (node (ref "R20") (pin "1") (pinfunction "1_1") (pintype "passive"))
      (node (ref "SHIELD") (pin "21") (pinfunction "21(SCL)_21") (pintype "bidirectional"))
    )
    (net (code "132") (name "SDA") (class "Default")
      (node (ref "I2C") (pin "3") (pinfunction "3_3") (pintype "passive"))
      (node (ref "R19") (pin "1") (pinfunction "1_1") (pintype "passive"))
      (node (ref "SHIELD") (pin "20") (pinfunction "20(SDA)_20") (pintype "bidirectional"))
    )
    (net (code "133") (name "THERM0") (class "Default")
      (node (ref "C12") (pin "2") (pinfunction "2_2") (pintype "passive"))
      (node (ref "R1") (pin "1") (pinfunction "1_1") (pintype "passive"))
      (node (ref "SHIELD") (pin "A13") (pinfunction "A13_A13") (pintype "bidirectional"))
      (node (ref "THERM0") (pin "2") (pinfunction "2_2") (pintype "bidirectional"))
    )
    (net (code "134") (name "THERM1") (class "Default")
      (node (ref "C13") (pin "2") (pinfunction "2_2") (pintype "passive"))
      (node (ref "R2") (pin "1") (pinfunction "1_1") (pintype "passive"))
      (node (ref "SHIELD") (pin "A14") (pinfunction "A14_A14") (pintype "bidirectional"))
      (node (ref "THERM1") (pin "2") (pinfunction "2_2") (pintype "bidirectional"))
    )
    (net (code "135") (name "THERM2") (class "Default")
      (node (ref "C14") (pin "2") (pinfunction "2_2") (pintype "passive"))
      (node (ref "R3") (pin "1") (pinfunction "1_1") (pintype "passive"))
      (node (ref "SHIELD") (pin "A15") (pinfunction "A15_A15") (pintype "bidirectional"))
      (node (ref "THERM2") (pin "2") (pinfunction "2_2") (pintype "bidirectional"))
    )
    (net (code "136") (name "VM") (class "Default")
      (node (ref "C10") (pin "2") (pinfunction "2_2") (pintype "passive"))
      (node (ref "C11") (pin "1") (pinfunction "1_1") (pintype "passive"))
      (node (ref "C15") (pin "2") (pinfunction "2_2") (pintype "passive"))
      (node (ref "C16") (pin "1") (pinfunction "1_1") (pintype "passive"))
      (node (ref "C18") (pin "2") (pinfunction "2_2") (pintype "passive"))
      (node (ref "C19") (pin "1") (pinfunction "1_1") (pintype "passive"))
      (node (ref "C20") (pin "2") (pinfunction "2_2") (pintype "passive"))
      (node (ref "C24") (pin "1") (pinfunction "1_1") (pintype "passive"))
      (node (ref "C26") (pin "2") (pinfunction "2_2") (pintype "passive"))
      (node (ref "C27") (pin "1") (pinfunction "1_1") (pintype "passive"))
      (node (ref "C28") (pin "2") (pinfunction "2_2") (pintype "passive"))
      (node (ref "C32") (pin "1") (pinfunction "1_1") (pintype "passive"))
      (node (ref "C34") (pin "2") (pinfunction "2_2") (pintype "passive"))
      (node (ref "C35") (pin "1") (pinfunction "1_1") (pintype "passive"))
      (node (ref "C36") (pin "2") (pinfunction "2_2") (pintype "passive"))
      (node (ref "C43") (pin "+") (pinfunction "+_+") (pintype "passive"))
      (node (ref "C7") (pin "1") (pinfunction "1_1") (pintype "passive"))
      (node (ref "D2") (pin "C") (pinfunction "C_C") (pintype "bidirectional"))
      (node (ref "D4") (pin "C") (pinfunction "C_C") (pintype "bidirectional"))
      (node (ref "D5") (pin "C") (pinfunction "C_C") (pintype "bidirectional"))
      (node (ref "D6") (pin "C") (pinfunction "C_C") (pintype "bidirectional"))
      (node (ref "D_HB1") (pin "C") (pinfunction "C_C") (pintype "bidirectional"))
      (node (ref "D_HB2") (pin "C") (pinfunction "C_C") (pintype "bidirectional"))
      (node (ref "EX_0") (pin "P$2") (pinfunction "2_P$2") (pintype "bidirectional"))
      (node (ref "F1") (pin "P$2") (pinfunction "2_P$2") (pintype "passive"))
      (node (ref "FAN") (pin "P$2") (pinfunction "2_P$2") (pintype "bidirectional"))
      (node (ref "LED3") (pin "A") (pinfunction "A_A") (pintype "passive"))
      (node (ref "R21") (pin "2") (pinfunction "2_2") (pintype "passive"))
      (node (ref "R26") (pin "2") (pinfunction "2_2") (pintype "passive"))
      (node (ref "TMC1") (pin "21") (pinfunction "VS_21") (pintype "bidirectional"))
      (node (ref "TMC1") (pin "39") (pinfunction "VSA_39") (pintype "bidirectional"))
      (node (ref "TMC1") (pin "40") (pinfunction "VS_40") (pintype "bidirectional"))
      (node (ref "TMC2") (pin "21") (pinfunction "VS_21") (pintype "bidirectional"))
      (node (ref "TMC2") (pin "39") (pinfunction "VSA_39") (pintype "bidirectional"))
      (node (ref "TMC2") (pin "40") (pinfunction "VS_40") (pintype "bidirectional"))
      (node (ref "TMC3") (pin "21") (pinfunction "VS_21") (pintype "bidirectional"))
      (node (ref "TMC3") (pin "39") (pinfunction "VSA_39") (pintype "bidirectional"))
      (node (ref "TMC3") (pin "40") (pinfunction "VS_40") (pintype "bidirectional"))
      (node (ref "TMC5130") (pin "21") (pinfunction "VS_21") (pintype "bidirectional"))
      (node (ref "TMC5130") (pin "39") (pinfunction "VSA_39") (pintype "bidirectional"))
      (node (ref "TMC5130") (pin "40") (pinfunction "VS_40") (pintype "bidirectional"))
      (node (ref "VM0") (pin "2") (pinfunction "2_2") (pintype "bidirectional"))
      (node (ref "VM1") (pin "2") (pinfunction "2_2") (pintype "bidirectional"))
    )
    (net (code "137") (name "V_HEATBED") (class "Default")
      (node (ref "C42") (pin "+") (pinfunction "+_+") (pintype "passive"))
      (node (ref "D_HB") (pin "C") (pinfunction "C_C") (pintype "bidirectional"))
      (node (ref "F2") (pin "P$2") (pinfunction "2_P$2") (pintype "passive"))
      (node (ref "HEATBED") (pin "P$2") (pinfunction "2_P$2") (pintype "bidirectional"))
      (node (ref "LED2") (pin "A") (pinfunction "A_A") (pintype "passive"))
      (node (ref "R24") (pin "2") (pinfunction "2_2") (pintype "passive"))
    )
    (net (code "138") (name "unconnected-(AUX-3-Pad8)") (class "Default")
      (node (ref "AUX-3") (pin "8") (pinfunction "8_8") (pintype "passive"))
    )
    (net (code "139") (name "unconnected-(SHIELD-14(TX3)-Pad14)") (class "Default")
      (node (ref "SHIELD") (pin "14") (pinfunction "14(TX3)_14") (pintype "bidirectional"))
    )
    (net (code "140") (name "unconnected-(SHIELD-15(RX3)-Pad15)") (class "Default")
      (node (ref "SHIELD") (pin "15") (pinfunction "15(RX3)_15") (pintype "bidirectional"))
    )
    (net (code "141") (name "unconnected-(SHIELD-18(TX1)-Pad18)") (class "Default")
      (node (ref "SHIELD") (pin "18") (pinfunction "18(TX1)_18") (pintype "bidirectional"))
    )
    (net (code "142") (name "unconnected-(SHIELD-19(RX1)-Pad19)") (class "Default")
      (node (ref "SHIELD") (pin "19") (pinfunction "19(RX1)_19") (pintype "bidirectional"))
    )
    (net (code "143") (name "unconnected-(SHIELD-A0(RX0)-PadA0)") (class "Default")
      (node (ref "SHIELD") (pin "A0") (pinfunction "A0(RX0)_A0") (pintype "bidirectional"))
    )
    (net (code "144") (name "unconnected-(SHIELD-A1(TX0)-PadA1)") (class "Default")
      (node (ref "SHIELD") (pin "A1") (pinfunction "A1(TX0)_A1") (pintype "bidirectional"))
    )
    (net (code "145") (name "unconnected-(SHIELD-Pad3.3V)") (class "Default")
      (node (ref "SHIELD") (pin "3.3V") (pinfunction "3.3V_3.3V") (pintype "bidirectional"))
    )
    (net (code "146") (name "unconnected-(SHIELD-Pad7)") (class "Default")
      (node (ref "SHIELD") (pin "7") (pinfunction "7_7") (pintype "bidirectional"))
    )
    (net (code "147") (name "unconnected-(SHIELD-Pad12)") (class "Default")
      (node (ref "SHIELD") (pin "12") (pinfunction "12_12") (pintype "bidirectional"))
    )
    (net (code "148") (name "unconnected-(SHIELD-Pad13)") (class "Default")
      (node (ref "SHIELD") (pin "13") (pinfunction "13_13") (pintype "bidirectional"))
    )
    (net (code "149") (name "unconnected-(SHIELD-Pad22)") (class "Default")
      (node (ref "SHIELD") (pin "22") (pinfunction "22_22") (pintype "bidirectional"))
    )
    (net (code "150") (name "unconnected-(SHIELD-Pad26)") (class "Default")
      (node (ref "SHIELD") (pin "26") (pinfunction "26_26") (pintype "bidirectional"))
    )
    (net (code "151") (name "unconnected-(SHIELD-Pad28)") (class "Default")
      (node (ref "SHIELD") (pin "28") (pinfunction "28_28") (pintype "bidirectional"))
    )
    (net (code "152") (name "unconnected-(SHIELD-Pad30)") (class "Default")
      (node (ref "SHIELD") (pin "30") (pinfunction "30_30") (pintype "bidirectional"))
    )
    (net (code "153") (name "unconnected-(SHIELD-PadA6)") (class "Default")
      (node (ref "SHIELD") (pin "A6") (pinfunction "A6_A6") (pintype "bidirectional"))
    )
    (net (code "154") (name "unconnected-(SHIELD-PadA7)") (class "Default")
      (node (ref "SHIELD") (pin "A7") (pinfunction "A7_A7") (pintype "bidirectional"))
    )
    (net (code "155") (name "unconnected-(SHIELD-PadAREF)") (class "Default")
      (node (ref "SHIELD") (pin "AREF") (pinfunction "AREF_AREF") (pintype "bidirectional"))
    )
    (net (code "156") (name "unconnected-(SHIELD-PadVIN)") (class "Default")
      (node (ref "SHIELD") (pin "VIN") (pinfunction "VIN_VIN") (pintype "bidirectional"))
    )
    (net (code "157") (name "unconnected-(TMC1-AIN_IREF-Pad30)") (class "Default")
      (node (ref "TMC1") (pin "30") (pinfunction "AIN_IREF_30") (pintype "bidirectional"))
    )
    (net (code "158") (name "unconnected-(TMC1-ENCA_DCIN_CFG5-Pad25)") (class "Default")
      (node (ref "TMC1") (pin "25") (pinfunction "ENCA_DCIN_CFG5_25") (pintype "bidirectional"))
    )
    (net (code "159") (name "unconnected-(TMC1-ENCB_DCEN_CFG4-Pad24)") (class "Default")
      (node (ref "TMC1") (pin "24") (pinfunction "ENCB_DCEN_CFG4_24") (pintype "bidirectional"))
    )
    (net (code "160") (name "unconnected-(TMC1-SPI_MODE-Pad12)") (class "Default")
      (node (ref "TMC1") (pin "12") (pinfunction "SPI_MODE_12") (pintype "bidirectional"))
    )
    (net (code "161") (name "unconnected-(TMC1-SWSEL-Pad28)") (class "Default")
      (node (ref "TMC1") (pin "28") (pinfunction "SWSEL_28") (pintype "bidirectional"))
    )
    (net (code "162") (name "unconnected-(TMC2-AIN_IREF-Pad30)") (class "Default")
      (node (ref "TMC2") (pin "30") (pinfunction "AIN_IREF_30") (pintype "bidirectional"))
    )
    (net (code "163") (name "unconnected-(TMC2-ENCA_DCIN_CFG5-Pad25)") (class "Default")
      (node (ref "TMC2") (pin "25") (pinfunction "ENCA_DCIN_CFG5_25") (pintype "bidirectional"))
    )
    (net (code "164") (name "unconnected-(TMC2-ENCB_DCEN_CFG4-Pad24)") (class "Default")
      (node (ref "TMC2") (pin "24") (pinfunction "ENCB_DCEN_CFG4_24") (pintype "bidirectional"))
    )
    (net (code "165") (name "unconnected-(TMC2-SPI_MODE-Pad12)") (class "Default")
      (node (ref "TMC2") (pin "12") (pinfunction "SPI_MODE_12") (pintype "bidirectional"))
    )
    (net (code "166") (name "unconnected-(TMC2-SWSEL-Pad28)") (class "Default")
      (node (ref "TMC2") (pin "28") (pinfunction "SWSEL_28") (pintype "bidirectional"))
    )
    (net (code "167") (name "unconnected-(TMC3-AIN_IREF-Pad30)") (class "Default")
      (node (ref "TMC3") (pin "30") (pinfunction "AIN_IREF_30") (pintype "bidirectional"))
    )
    (net (code "168") (name "unconnected-(TMC3-ENCA_DCIN_CFG5-Pad25)") (class "Default")
      (node (ref "TMC3") (pin "25") (pinfunction "ENCA_DCIN_CFG5_25") (pintype "bidirectional"))
    )
    (net (code "169") (name "unconnected-(TMC3-ENCB_DCEN_CFG4-Pad24)") (class "Default")
      (node (ref "TMC3") (pin "24") (pinfunction "ENCB_DCEN_CFG4_24") (pintype "bidirectional"))
    )
    (net (code "170") (name "unconnected-(TMC3-SPI_MODE-Pad12)") (class "Default")
      (node (ref "TMC3") (pin "12") (pinfunction "SPI_MODE_12") (pintype "bidirectional"))
    )
    (net (code "171") (name "unconnected-(TMC3-SWSEL-Pad28)") (class "Default")
      (node (ref "TMC3") (pin "28") (pinfunction "SWSEL_28") (pintype "bidirectional"))
    )
    (net (code "172") (name "unconnected-(TMC5130-AIN_IREF-Pad30)") (class "Default")
      (node (ref "TMC5130") (pin "30") (pinfunction "AIN_IREF_30") (pintype "bidirectional"))
    )
    (net (code "173") (name "unconnected-(TMC5130-ENCA_DCIN_CFG5-Pad25)") (class "Default")
      (node (ref "TMC5130") (pin "25") (pinfunction "ENCA_DCIN_CFG5_25") (pintype "bidirectional"))
    )
    (net (code "174") (name "unconnected-(TMC5130-ENCB_DCEN_CFG4-Pad24)") (class "Default")
      (node (ref "TMC5130") (pin "24") (pinfunction "ENCB_DCEN_CFG4_24") (pintype "bidirectional"))
    )
    (net (code "175") (name "unconnected-(TMC5130-SPI_MODE-Pad12)") (class "Default")
      (node (ref "TMC5130") (pin "12") (pinfunction "SPI_MODE_12") (pintype "bidirectional"))
    )
    (net (code "176") (name "unconnected-(TMC5130-SWSEL-Pad28)") (class "Default")
      (node (ref "TMC5130") (pin "28") (pinfunction "SWSEL_28") (pintype "bidirectional"))
    )
  )
)
